# axiom_beta_plugin_module_TE0714_SDI_v0_7.net
KiCad netlist of a schematic drawn in EAGLE
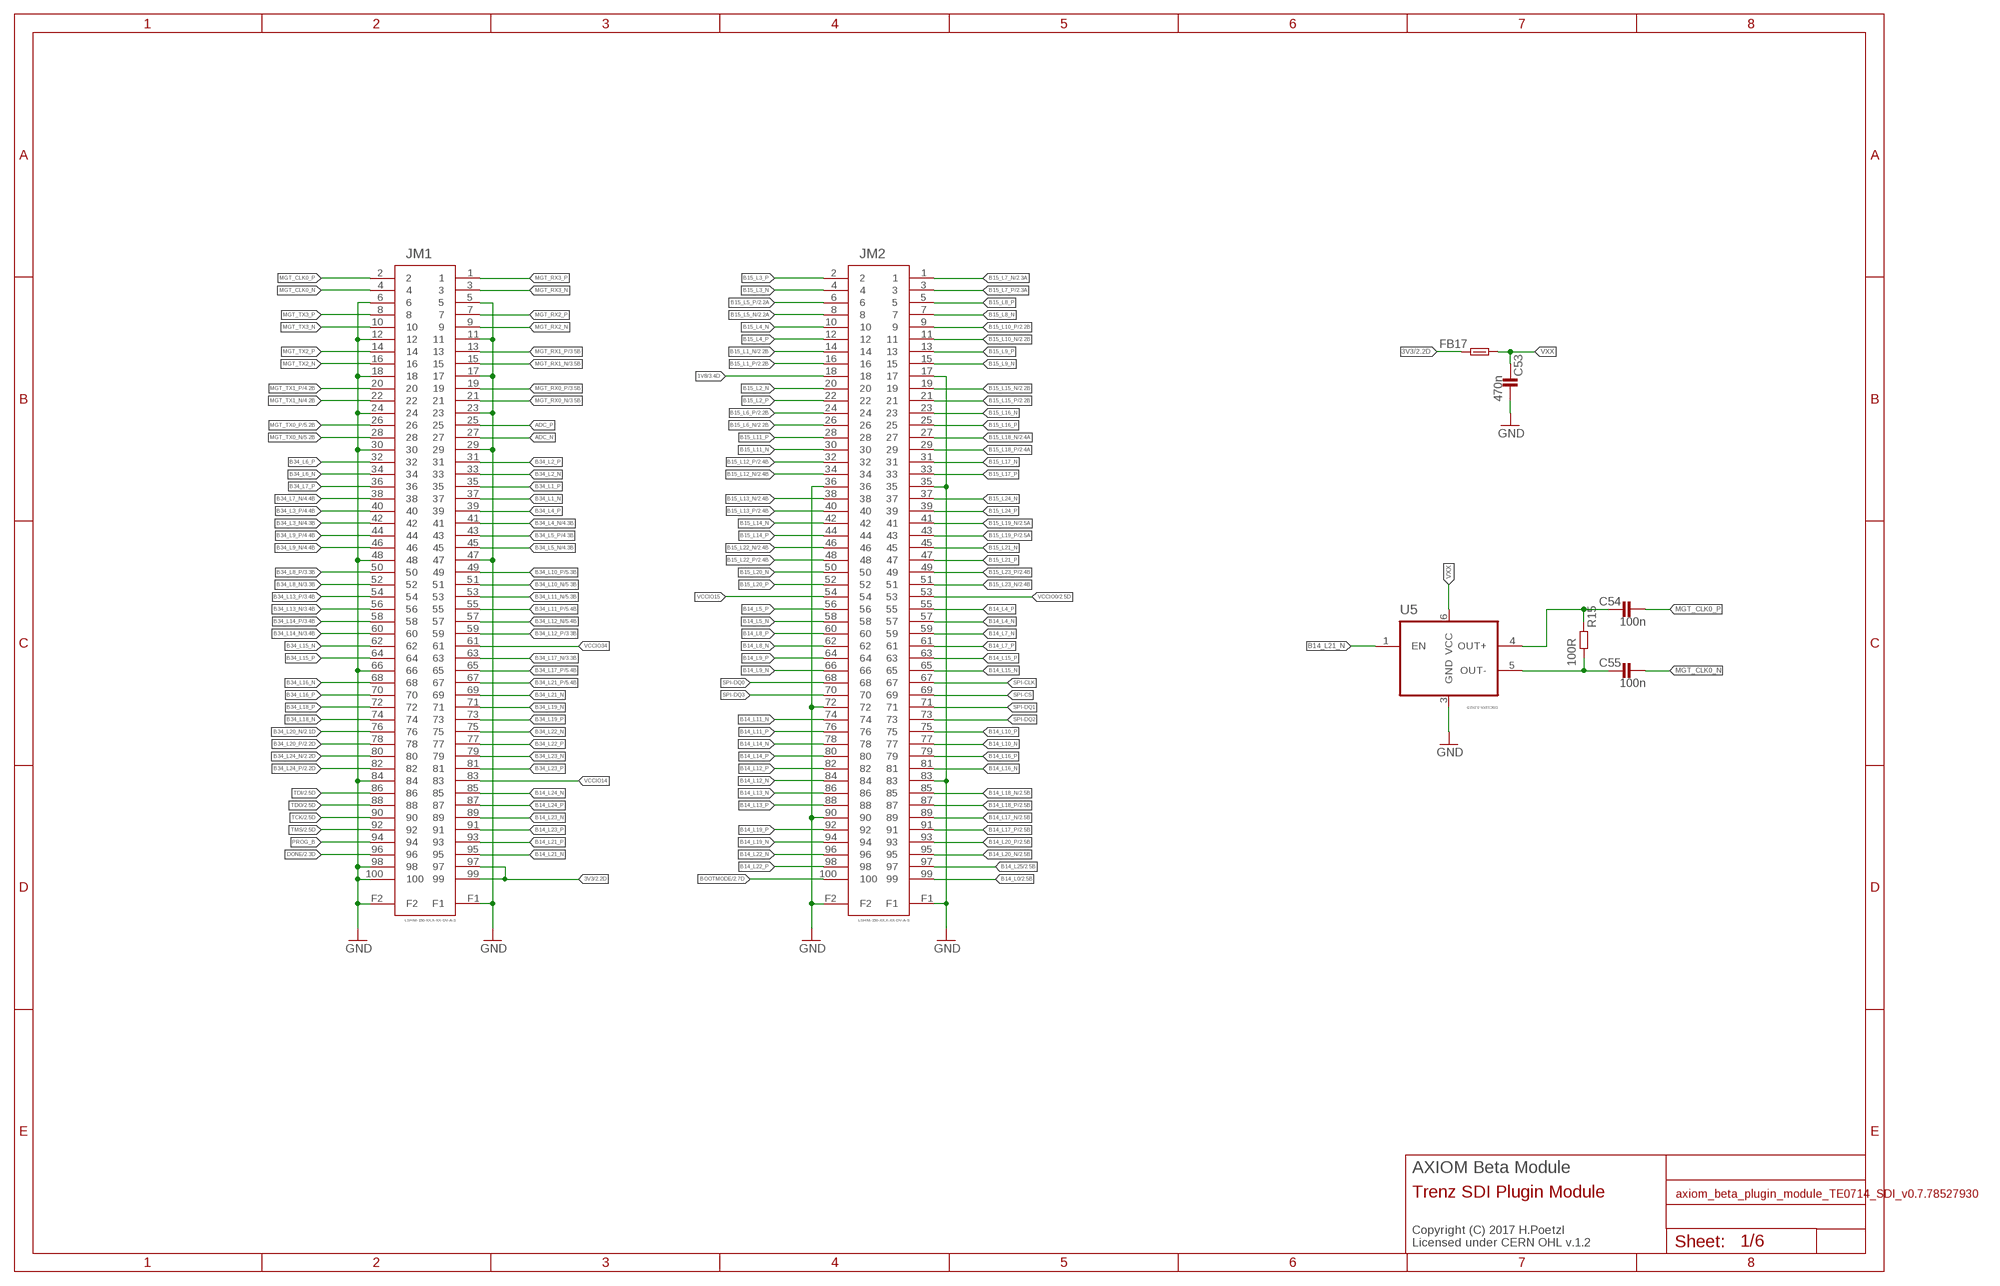
[diagram p0: schematic, sheet 1]
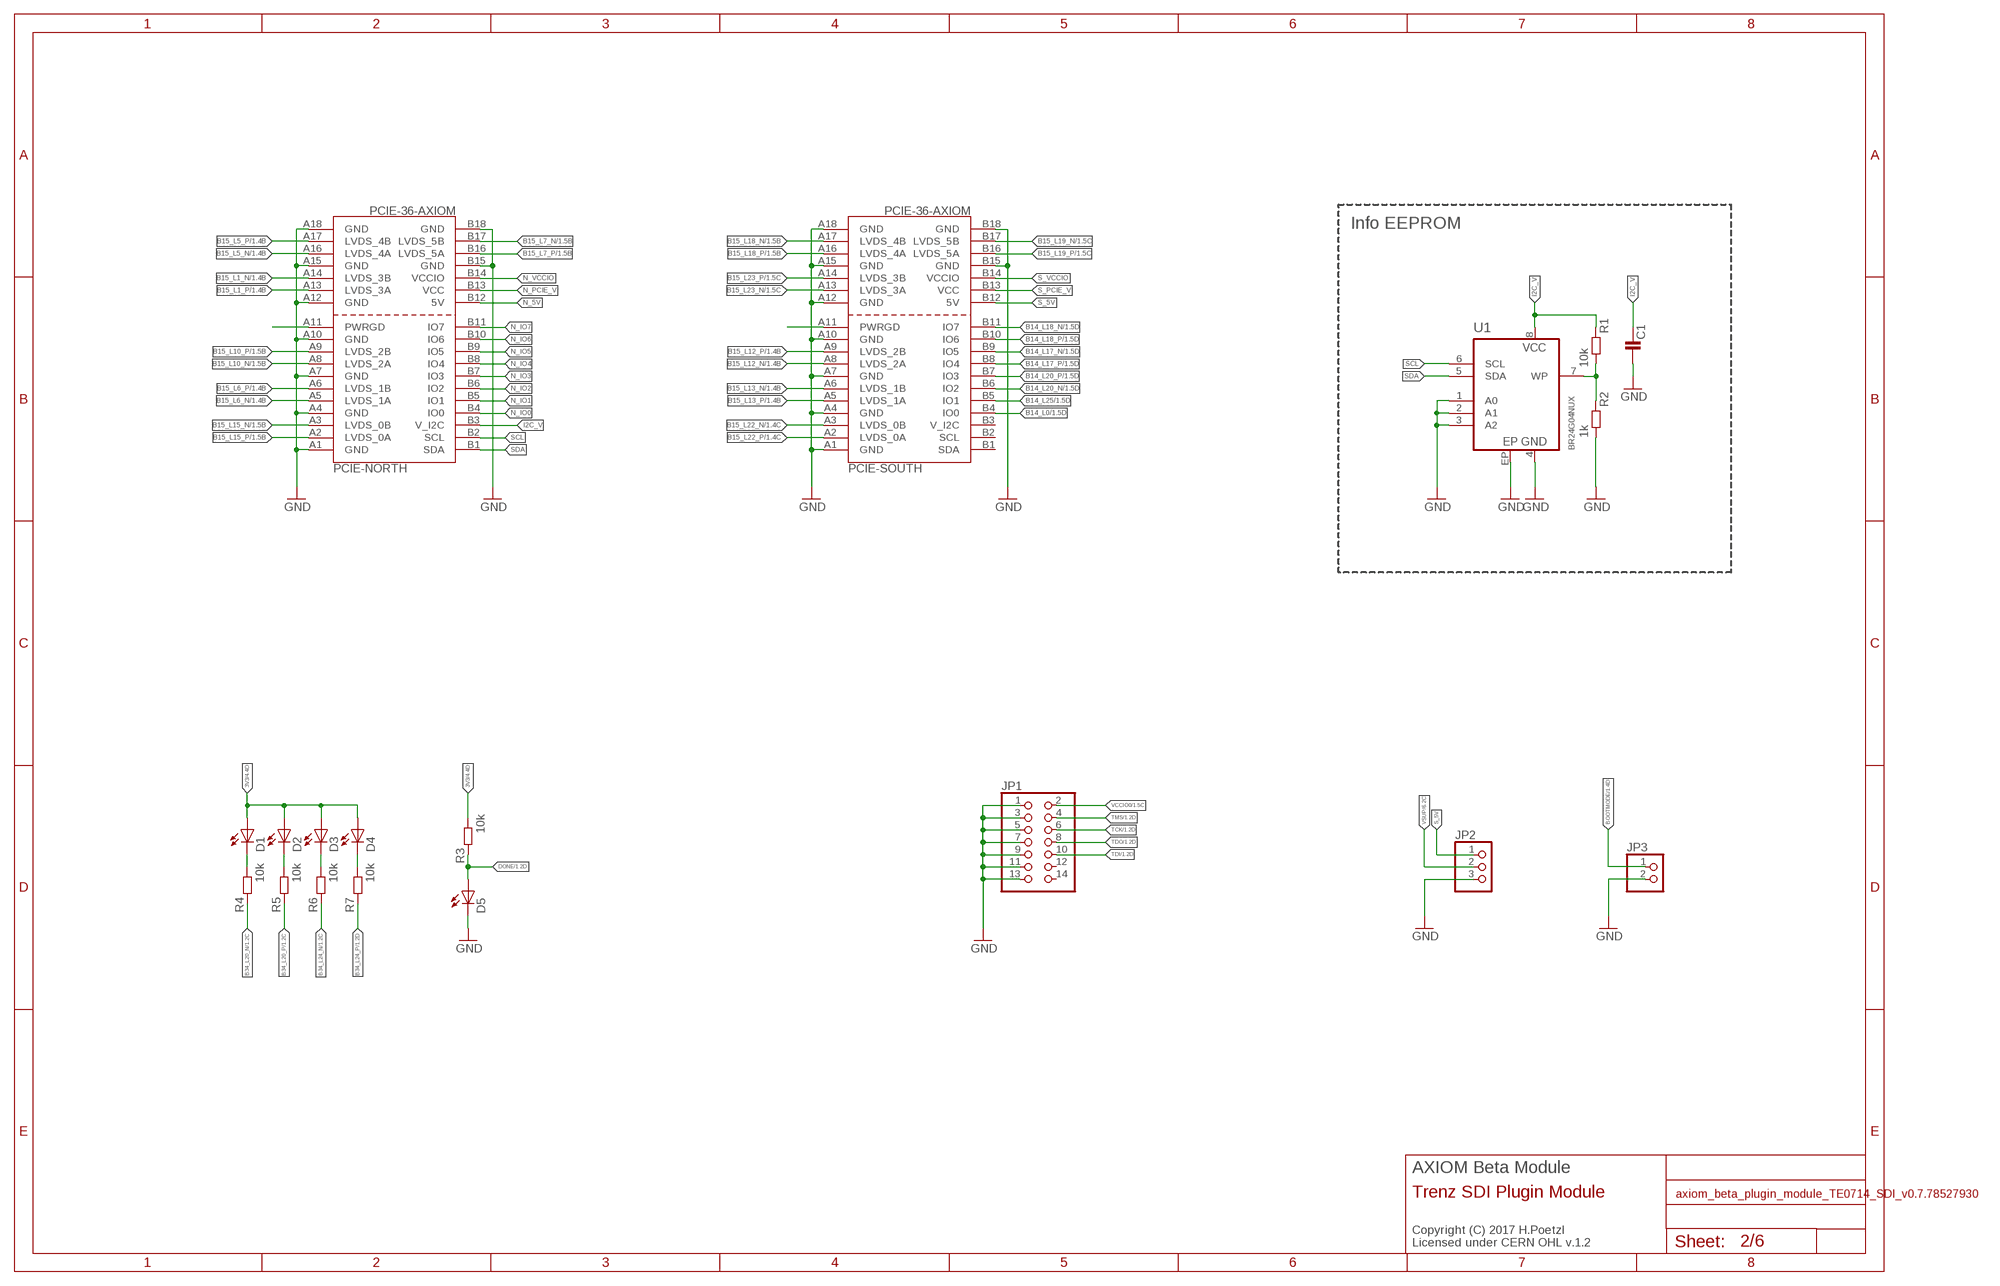
[diagram p1: schematic, sheet 2]
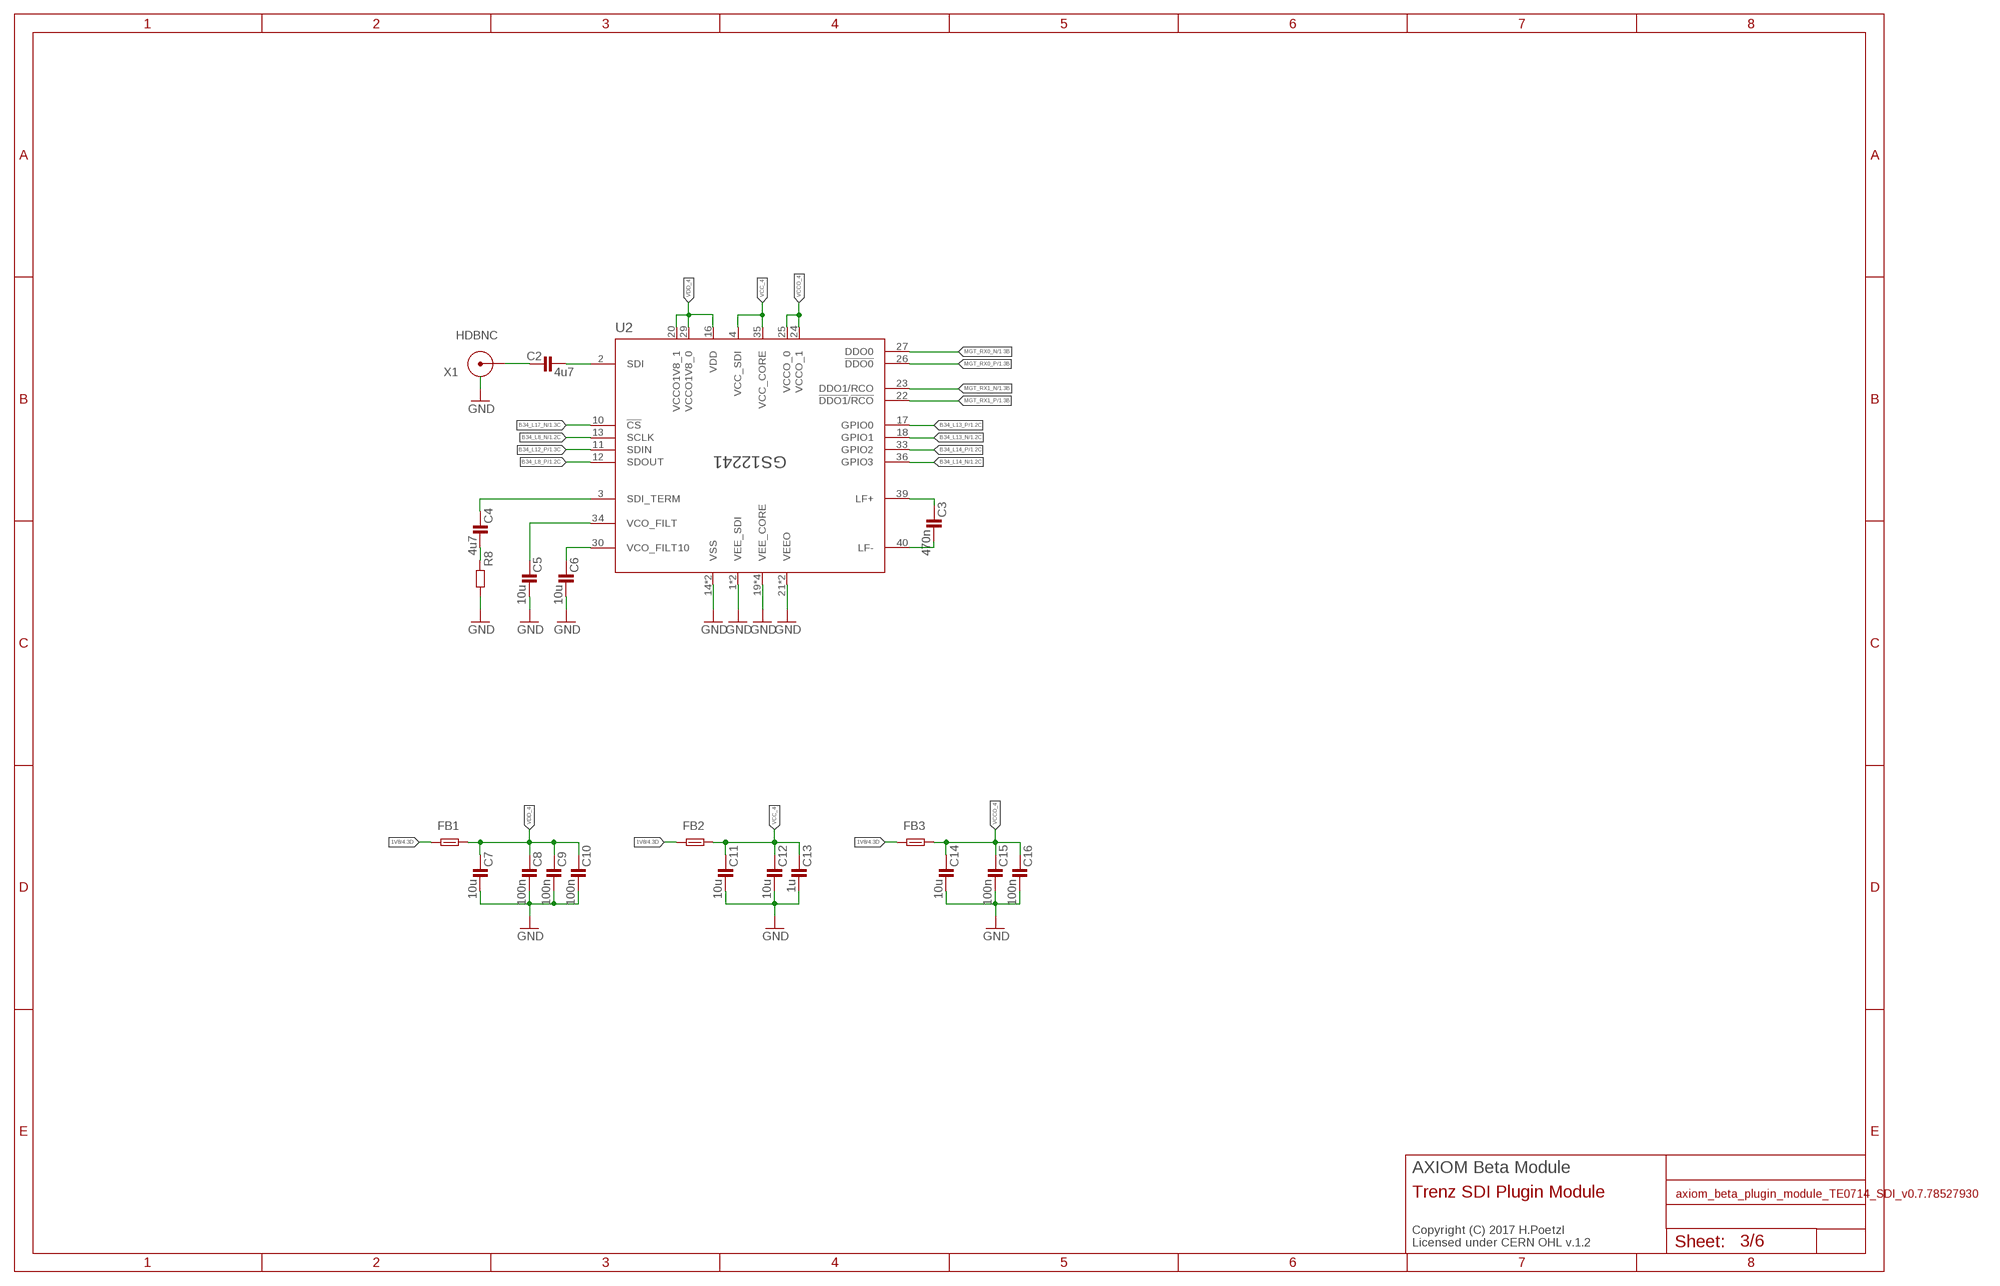
[diagram p2: schematic, sheet 3]
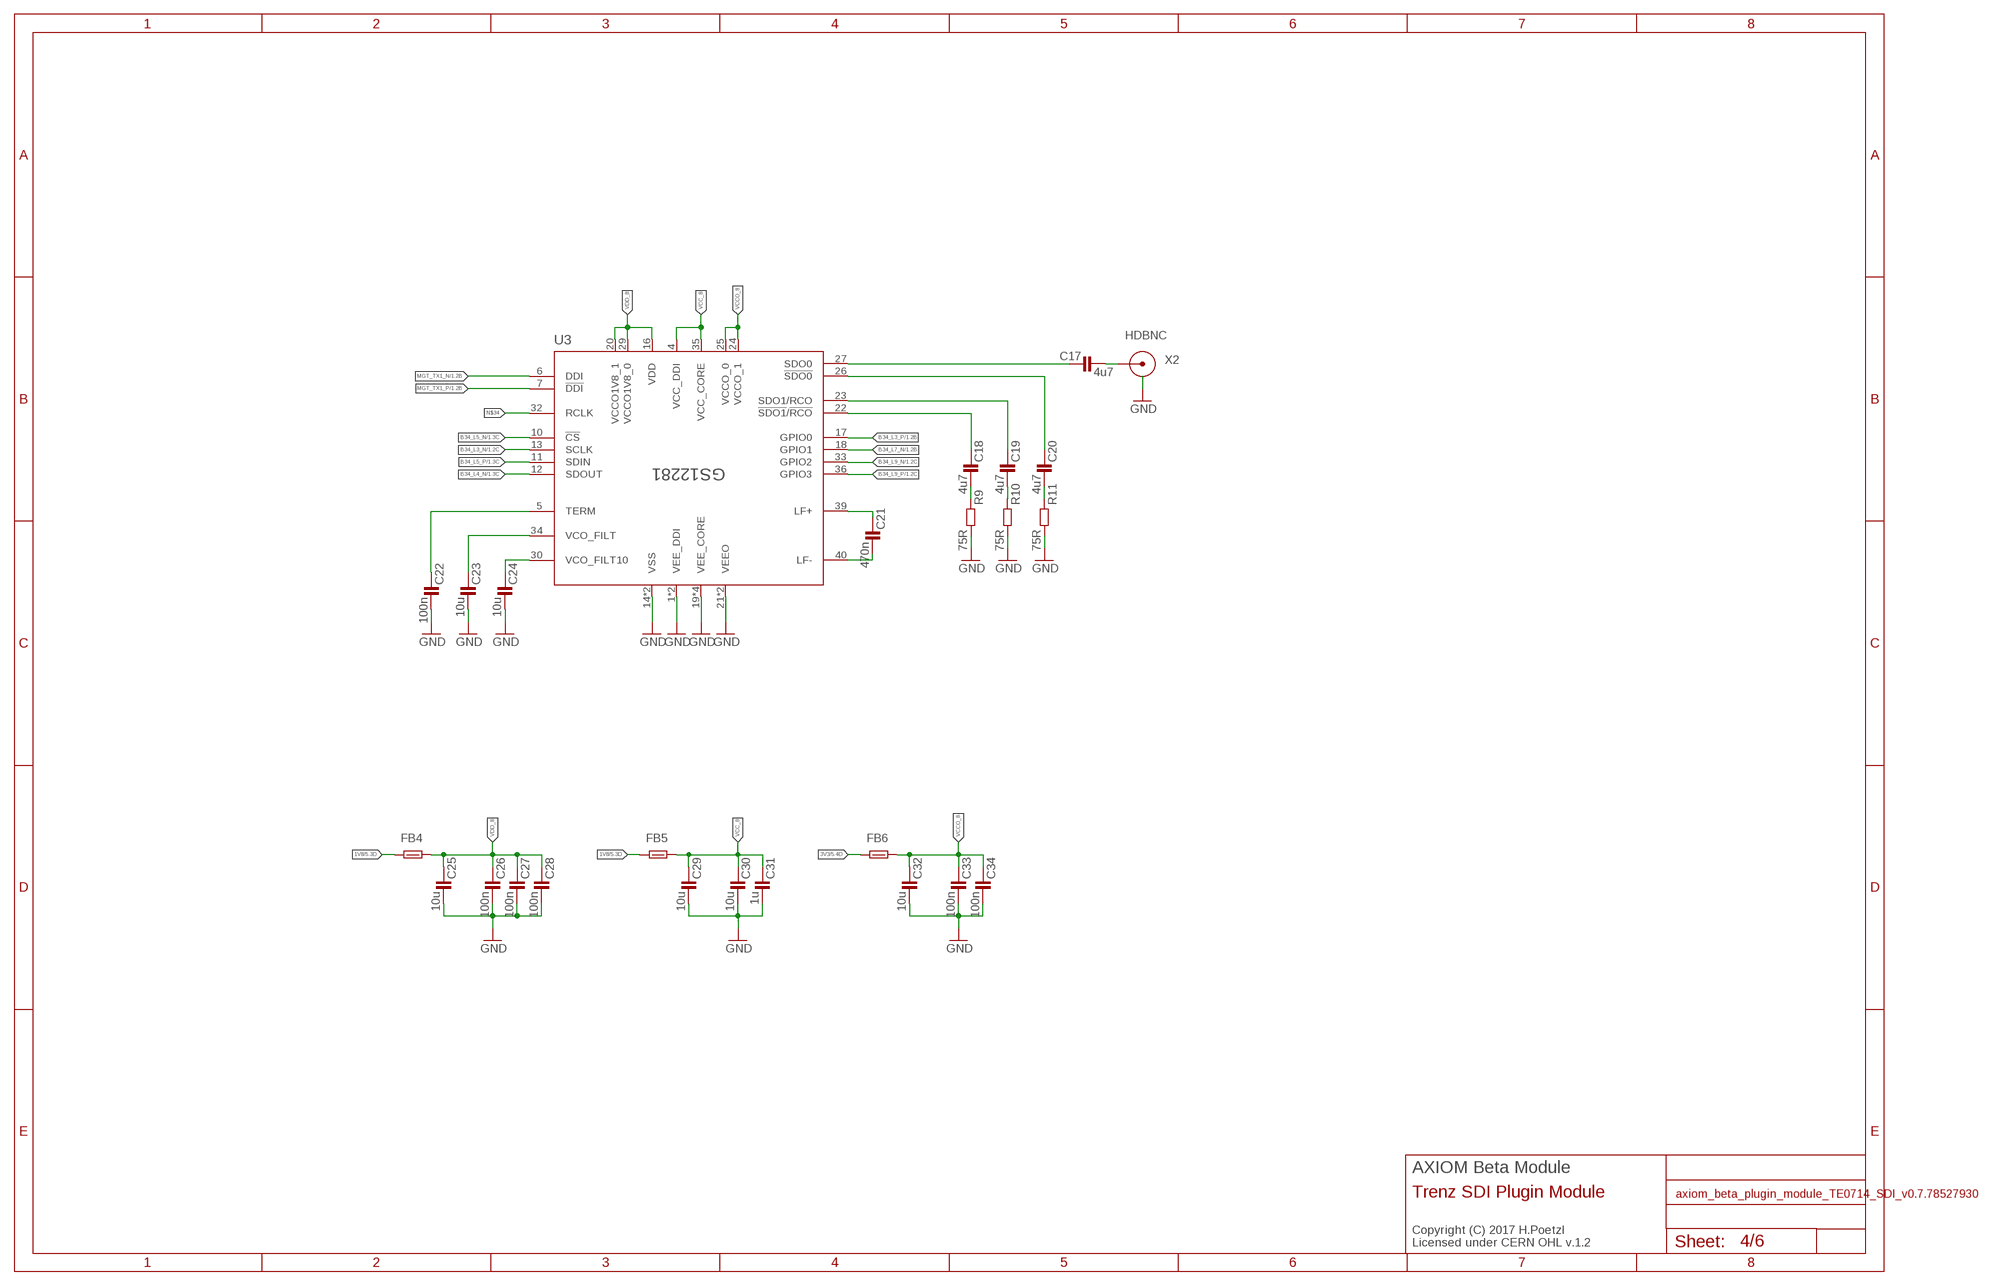
[diagram p3: schematic, sheet 4]
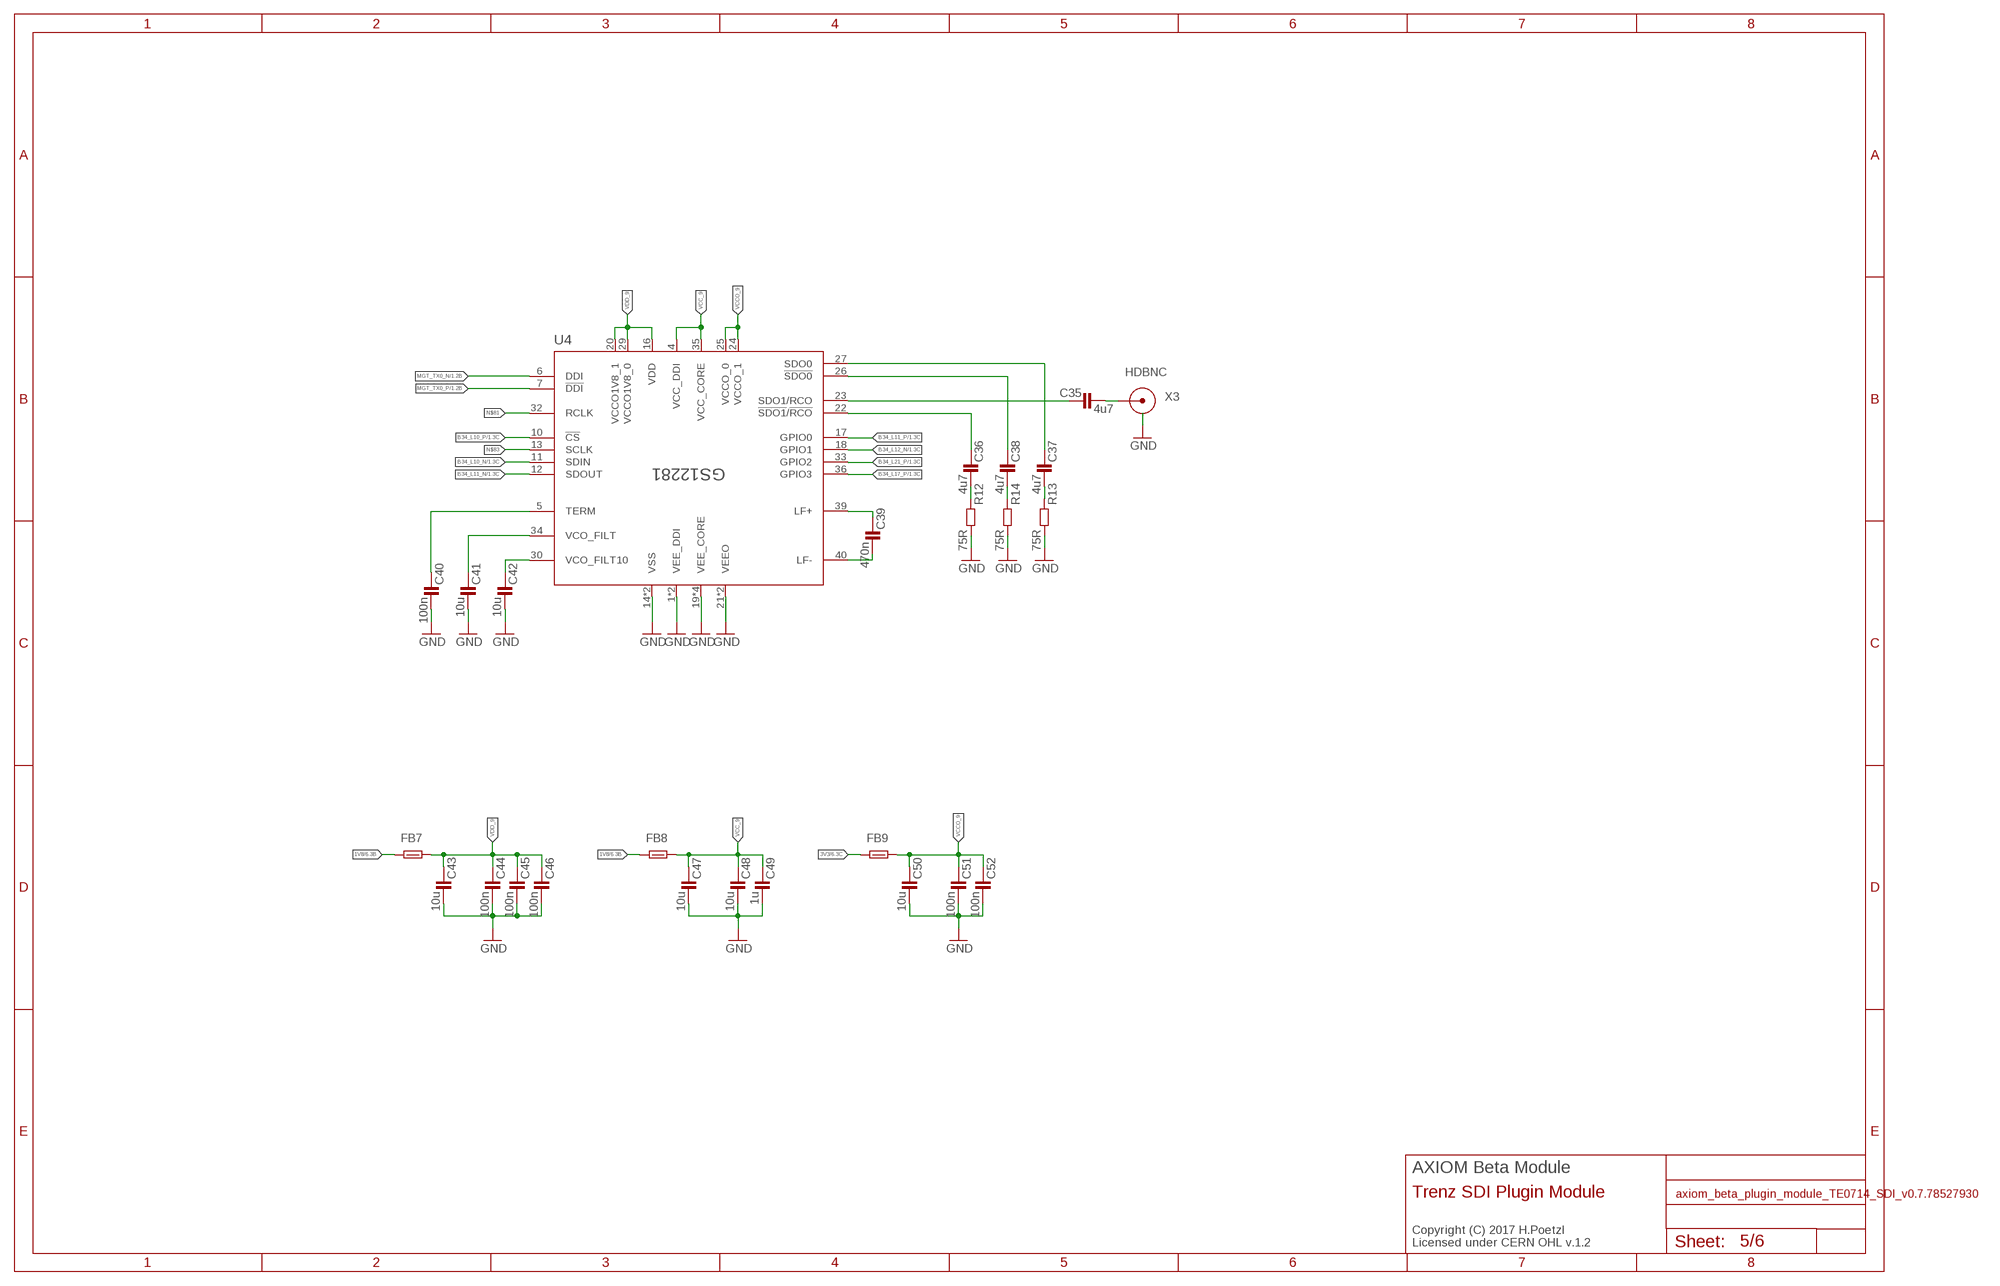
[diagram p4: schematic, sheet 5]
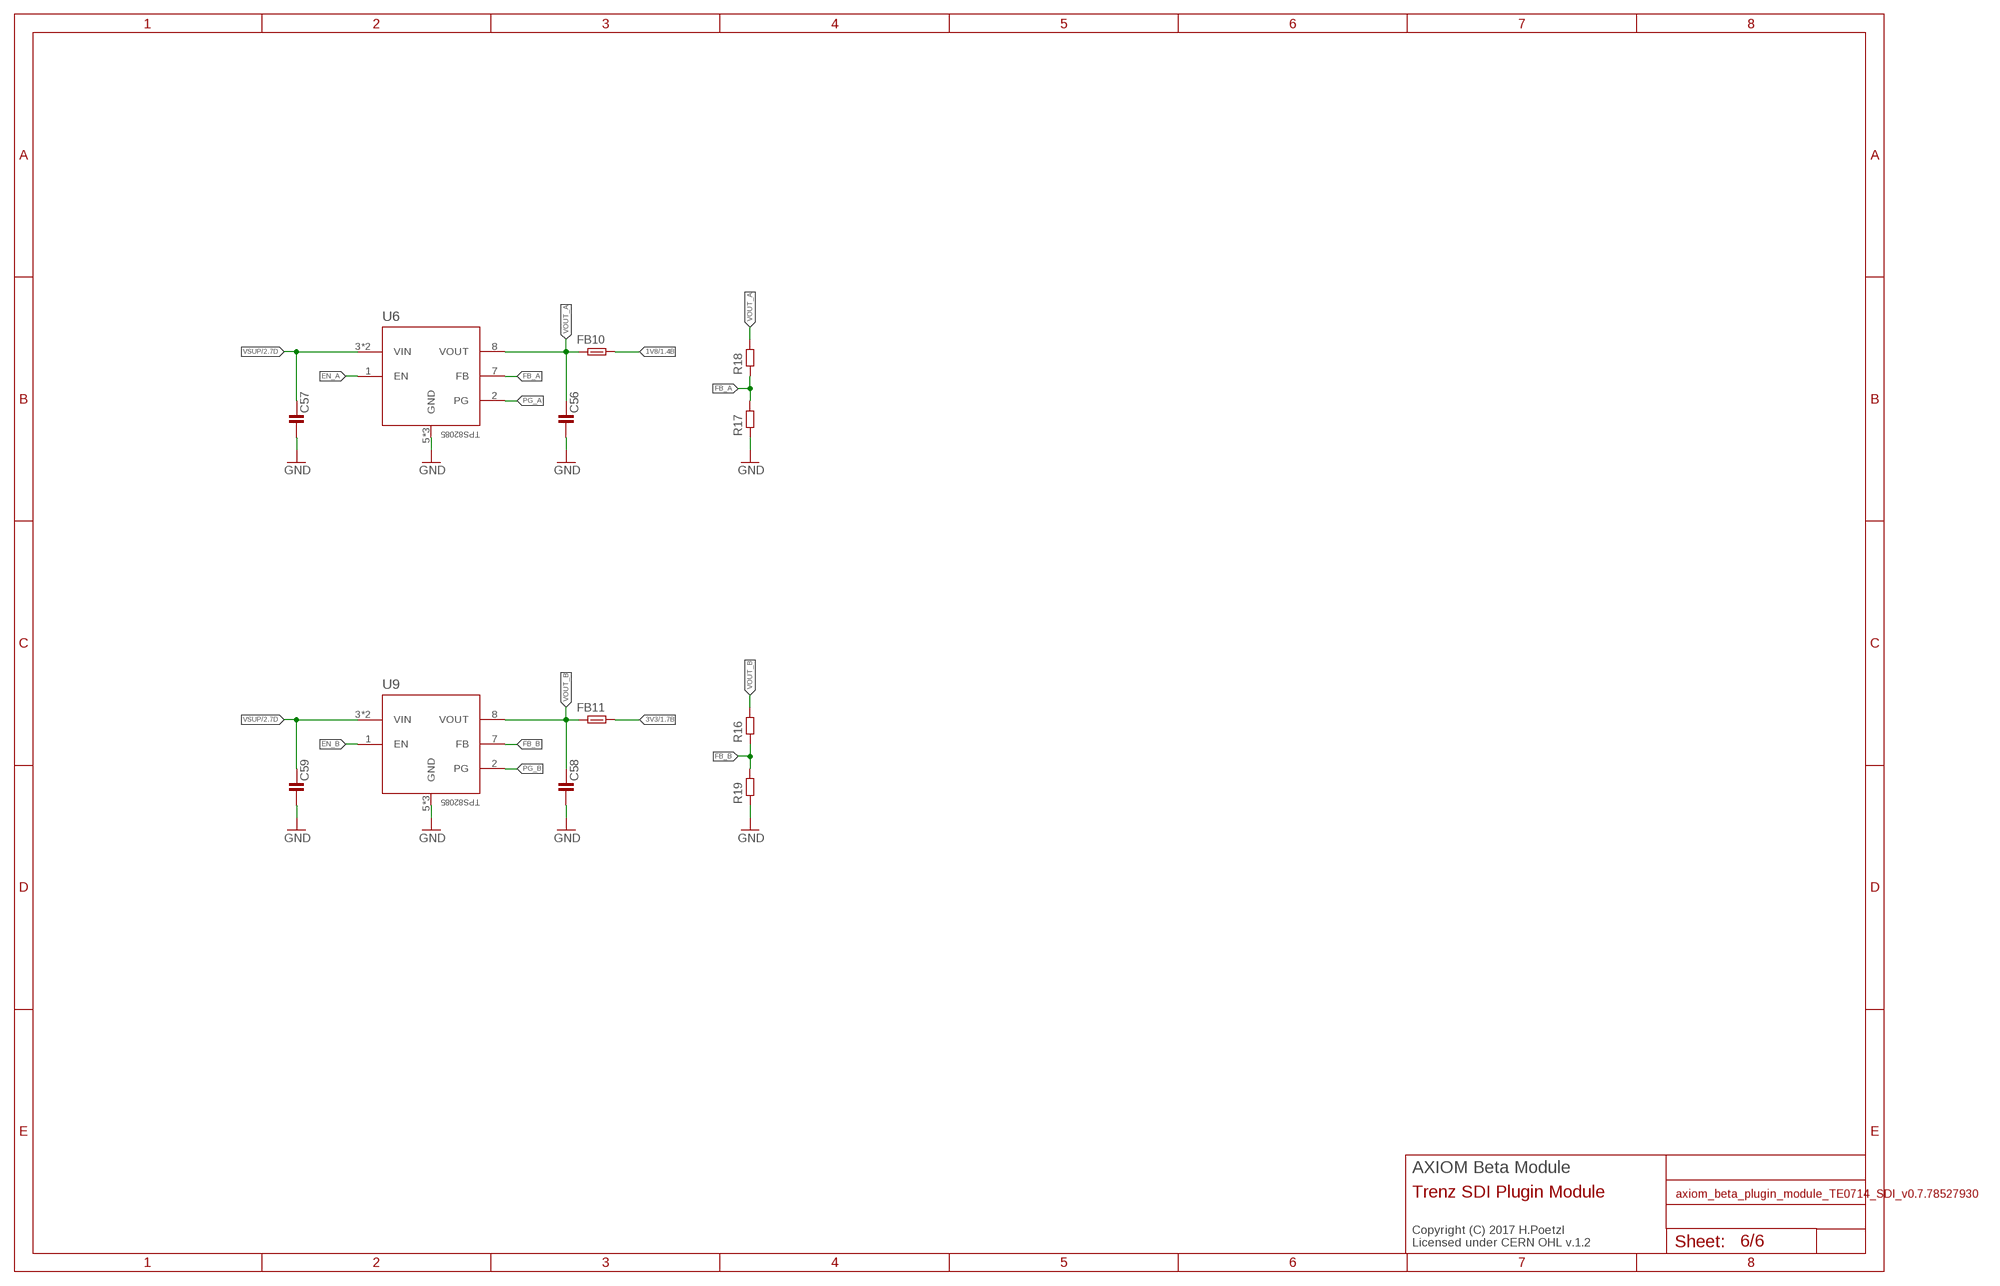
[diagram p5: schematic, sheet 6]

(export (version "E")
  (design (tool "Eeschema 10.0.6"))
  (components
    (comp (ref "C56")
      (value "C0603-C")
      (footprint "eagle-import:0603-C")
      (libsource (lib "eagle-import") (part "C0603-C"))
    )
    (comp (ref "C57")
      (value "C0603-C")
      (footprint "eagle-import:0603-C")
      (libsource (lib "eagle-import") (part "C0603-C"))
    )
    (comp (ref "C58")
      (value "C0603-C")
      (footprint "eagle-import:0603-C")
      (libsource (lib "eagle-import") (part "C0603-C"))
    )
    (comp (ref "C59")
      (value "C0603-C")
      (footprint "eagle-import:0603-C")
      (libsource (lib "eagle-import") (part "C0603-C"))
    )
    (comp (ref "FB10")
      (value "FB0603-C")
      (footprint "eagle-import:0603-C")
      (libsource (lib "eagle-import") (part "FB0603-C"))
    )
    (comp (ref "FB11")
      (value "FB0603-C")
      (footprint "eagle-import:0603-C")
      (libsource (lib "eagle-import") (part "FB0603-C"))
    )
    (comp (ref "R16")
      (value "R0201-C")
      (footprint "eagle-import:0201-C")
      (libsource (lib "eagle-import") (part "R0201-C"))
    )
    (comp (ref "R17")
      (value "R0201-C")
      (footprint "eagle-import:0201-C")
      (libsource (lib "eagle-import") (part "R0201-C"))
    )
    (comp (ref "R18")
      (value "R0201-C")
      (footprint "eagle-import:0201-C")
      (libsource (lib "eagle-import") (part "R0201-C"))
    )
    (comp (ref "R19")
      (value "R0201-C")
      (footprint "eagle-import:0201-C")
      (libsource (lib "eagle-import") (part "R0201-C"))
    )
    (comp (ref "U6")
      (value "TPS82085")
      (footprint "eagle-import:MICROSIP")
      (libsource (lib "eagle-import") (part "TPS82085"))
    )
    (comp (ref "U9")
      (value "TPS82085")
      (footprint "eagle-import:MICROSIP")
      (libsource (lib "eagle-import") (part "TPS82085"))
    )
    (comp (ref "C17")
      (value "4u7")
      (footprint "eagle-import:0402-C")
      (libsource (lib "eagle-import") (part "C0402-C"))
    )
    (comp (ref "C18")
      (value "4u7")
      (footprint "eagle-import:0402-C")
      (libsource (lib "eagle-import") (part "C0402-C"))
    )
    (comp (ref "C19")
      (value "4u7")
      (footprint "eagle-import:0402-C")
      (libsource (lib "eagle-import") (part "C0402-C"))
    )
    (comp (ref "C20")
      (value "4u7")
      (footprint "eagle-import:0402-C")
      (libsource (lib "eagle-import") (part "C0402-C"))
    )
    (comp (ref "C21")
      (value "470n")
      (footprint "eagle-import:0201-C")
      (libsource (lib "eagle-import") (part "C0201-C"))
    )
    (comp (ref "C22")
      (value "100n")
      (footprint "eagle-import:0201-C")
      (libsource (lib "eagle-import") (part "C0201-C"))
    )
    (comp (ref "C23")
      (value "10u")
      (footprint "eagle-import:0201-C")
      (libsource (lib "eagle-import") (part "C0201-C"))
    )
    (comp (ref "C24")
      (value "10u")
      (footprint "eagle-import:0402-C")
      (libsource (lib "eagle-import") (part "C0402-C"))
    )
    (comp (ref "C25")
      (value "10u")
      (footprint "eagle-import:0402-C")
      (libsource (lib "eagle-import") (part "C0402-C"))
    )
    (comp (ref "C26")
      (value "100n")
      (footprint "eagle-import:0201-C")
      (libsource (lib "eagle-import") (part "C0201-C"))
    )
    (comp (ref "C27")
      (value "100n")
      (footprint "eagle-import:0201-C")
      (libsource (lib "eagle-import") (part "C0201-C"))
    )
    (comp (ref "C28")
      (value "100n")
      (footprint "eagle-import:0201-C")
      (libsource (lib "eagle-import") (part "C0201-C"))
    )
    (comp (ref "C29")
      (value "10u")
      (footprint "eagle-import:0402-C")
      (libsource (lib "eagle-import") (part "C0402-C"))
    )
    (comp (ref "C30")
      (value "10u")
      (footprint "eagle-import:0402-C")
      (libsource (lib "eagle-import") (part "C0402-C"))
    )
    (comp (ref "C31")
      (value "1u")
      (footprint "eagle-import:0201-C")
      (libsource (lib "eagle-import") (part "C0201-C"))
    )
    (comp (ref "C32")
      (value "10u")
      (footprint "eagle-import:0402-C")
      (libsource (lib "eagle-import") (part "C0402-C"))
    )
    (comp (ref "C33")
      (value "100n")
      (footprint "eagle-import:0201-C")
      (libsource (lib "eagle-import") (part "C0201-C"))
    )
    (comp (ref "C34")
      (value "100n")
      (footprint "eagle-import:0201-C")
      (libsource (lib "eagle-import") (part "C0201-C"))
    )
    (comp (ref "FB4")
      (value "FB0402-C")
      (footprint "eagle-import:0402-C")
      (libsource (lib "eagle-import") (part "FB0402-C"))
    )
    (comp (ref "FB5")
      (value "FB0402-C")
      (footprint "eagle-import:0402-C")
      (libsource (lib "eagle-import") (part "FB0402-C"))
    )
    (comp (ref "FB6")
      (value "FB0402-C")
      (footprint "eagle-import:0402-C")
      (libsource (lib "eagle-import") (part "FB0402-C"))
    )
    (comp (ref "R9")
      (value "75R")
      (footprint "eagle-import:0201-C")
      (libsource (lib "eagle-import") (part "R0201-C"))
    )
    (comp (ref "R10")
      (value "75R")
      (footprint "eagle-import:0201-C")
      (libsource (lib "eagle-import") (part "R0201-C"))
    )
    (comp (ref "R11")
      (value "75R")
      (footprint "eagle-import:0201-C")
      (libsource (lib "eagle-import") (part "R0201-C"))
    )
    (comp (ref "U3")
      (value "GS12281")
      (footprint "eagle-import:UQFN40P600X400X100-41N")
      (libsource (lib "eagle-import") (part "GS12281"))
    )
    (comp (ref "X2")
      (value "HDBNC")
      (footprint "eagle-import:HDBNC_EDGE_2SIDE")
      (libsource (lib "eagle-import") (part "HDBNC"))
    )
    (comp (ref "C1")
      (value "C0402-B")
      (footprint "eagle-import:0402-B")
      (libsource (lib "eagle-import") (part "C0402-B"))
    )
    (comp (ref "D1")
      (value "LED")
      (footprint "eagle-import:CHIPLED_0603")
      (libsource (lib "eagle-import") (part "LED"))
    )
    (comp (ref "D2")
      (value "LED")
      (footprint "eagle-import:CHIPLED_0603")
      (libsource (lib "eagle-import") (part "LED"))
    )
    (comp (ref "D3")
      (value "LED")
      (footprint "eagle-import:CHIPLED_0603")
      (libsource (lib "eagle-import") (part "LED"))
    )
    (comp (ref "D4")
      (value "LED")
      (footprint "eagle-import:CHIPLED_0603")
      (libsource (lib "eagle-import") (part "LED"))
    )
    (comp (ref "D5")
      (value "LED")
      (footprint "eagle-import:CHIPLED_0603")
      (libsource (lib "eagle-import") (part "LED"))
    )
    (comp (ref "JP1")
      (value "PINHD-2X07_2.00")
      (footprint "eagle-import:2X07M")
      (libsource (lib "eagle-import") (part "PINHD-2X07_2.00"))
    )
    (comp (ref "JP2")
      (value "PINHD-1X03_2.54-90°-S")
      (footprint "eagle-import:1X03_90-S")
      (libsource (lib "eagle-import") (part "PINHD-1X03_2.54-90°-S"))
    )
    (comp (ref "JP3")
      (value "PINHD-1X02_2.54-S")
      (footprint "eagle-import:1X02-S")
      (libsource (lib "eagle-import") (part "PINHD-1X02_2.54-S"))
    )
    (comp (ref "PCIE-NORTH")
      (value "PCIE-36-AXIOM")
      (footprint "eagle-import:PCIE-36-AXIOM")
      (libsource (lib "eagle-import") (part "PCIE-36-AXIOM"))
    )
    (comp (ref "PCIE-SOUTH")
      (value "PCIE-36-AXIOM")
      (footprint "eagle-import:PCIE-36-AXIOM")
      (libsource (lib "eagle-import") (part "PCIE-36-AXIOM"))
    )
    (comp (ref "R1")
      (value "10k")
      (footprint "eagle-import:0402-B")
      (libsource (lib "eagle-import") (part "R0402-B"))
    )
    (comp (ref "R2")
      (value "1k")
      (footprint "eagle-import:0402-B")
      (libsource (lib "eagle-import") (part "R0402-B"))
    )
    (comp (ref "R3")
      (value "10k")
      (footprint "eagle-import:0402-C")
      (libsource (lib "eagle-import") (part "R0402-C"))
    )
    (comp (ref "R4")
      (value "10k")
      (footprint "eagle-import:0402-C")
      (libsource (lib "eagle-import") (part "R0402-C"))
    )
    (comp (ref "R5")
      (value "10k")
      (footprint "eagle-import:0402-C")
      (libsource (lib "eagle-import") (part "R0402-C"))
    )
    (comp (ref "R6")
      (value "10k")
      (footprint "eagle-import:0402-C")
      (libsource (lib "eagle-import") (part "R0402-C"))
    )
    (comp (ref "R7")
      (value "10k")
      (footprint "eagle-import:0402-C")
      (libsource (lib "eagle-import") (part "R0402-C"))
    )
    (comp (ref "U1")
      (value "BR24G04NUX")
      (footprint "eagle-import:DFN200X300X100-9N")
      (libsource (lib "eagle-import") (part "BR24G04NUX"))
    )
    (comp (ref "C35")
      (value "4u7")
      (footprint "eagle-import:0402-C")
      (libsource (lib "eagle-import") (part "C0402-C"))
    )
    (comp (ref "C36")
      (value "4u7")
      (footprint "eagle-import:0402-C")
      (libsource (lib "eagle-import") (part "C0402-C"))
    )
    (comp (ref "C37")
      (value "4u7")
      (footprint "eagle-import:0402-C")
      (libsource (lib "eagle-import") (part "C0402-C"))
    )
    (comp (ref "C38")
      (value "4u7")
      (footprint "eagle-import:0402-C")
      (libsource (lib "eagle-import") (part "C0402-C"))
    )
    (comp (ref "C39")
      (value "470n")
      (footprint "eagle-import:0201-C")
      (libsource (lib "eagle-import") (part "C0201-C"))
    )
    (comp (ref "C40")
      (value "100n")
      (footprint "eagle-import:0201-C")
      (libsource (lib "eagle-import") (part "C0201-C"))
    )
    (comp (ref "C41")
      (value "10u")
      (footprint "eagle-import:0402-C")
      (libsource (lib "eagle-import") (part "C0402-C"))
    )
    (comp (ref "C42")
      (value "10u")
      (footprint "eagle-import:0402-C")
      (libsource (lib "eagle-import") (part "C0402-C"))
    )
    (comp (ref "C43")
      (value "10u")
      (footprint "eagle-import:0402-C")
      (libsource (lib "eagle-import") (part "C0402-C"))
    )
    (comp (ref "C44")
      (value "100n")
      (footprint "eagle-import:0201-C")
      (libsource (lib "eagle-import") (part "C0201-C"))
    )
    (comp (ref "C45")
      (value "100n")
      (footprint "eagle-import:0201-C")
      (libsource (lib "eagle-import") (part "C0201-C"))
    )
    (comp (ref "C46")
      (value "100n")
      (footprint "eagle-import:0201-C")
      (libsource (lib "eagle-import") (part "C0201-C"))
    )
    (comp (ref "C47")
      (value "10u")
      (footprint "eagle-import:0402-C")
      (libsource (lib "eagle-import") (part "C0402-C"))
    )
    (comp (ref "C48")
      (value "10u")
      (footprint "eagle-import:0402-C")
      (libsource (lib "eagle-import") (part "C0402-C"))
    )
    (comp (ref "C49")
      (value "1u")
      (footprint "eagle-import:0201-C")
      (libsource (lib "eagle-import") (part "C0201-C"))
    )
    (comp (ref "C50")
      (value "10u")
      (footprint "eagle-import:0402-C")
      (libsource (lib "eagle-import") (part "C0402-C"))
    )
    (comp (ref "C51")
      (value "100n")
      (footprint "eagle-import:0201-C")
      (libsource (lib "eagle-import") (part "C0201-C"))
    )
    (comp (ref "C52")
      (value "100n")
      (footprint "eagle-import:0201-C")
      (libsource (lib "eagle-import") (part "C0201-C"))
    )
    (comp (ref "FB7")
      (value "FB0402-C")
      (footprint "eagle-import:0402-C")
      (libsource (lib "eagle-import") (part "FB0402-C"))
    )
    (comp (ref "FB8")
      (value "FB0402-C")
      (footprint "eagle-import:0402-C")
      (libsource (lib "eagle-import") (part "FB0402-C"))
    )
    (comp (ref "FB9")
      (value "FB0402-C")
      (footprint "eagle-import:0402-C")
      (libsource (lib "eagle-import") (part "FB0402-C"))
    )
    (comp (ref "R12")
      (value "75R")
      (footprint "eagle-import:0201-C")
      (libsource (lib "eagle-import") (part "R0201-C"))
    )
    (comp (ref "R13")
      (value "75R")
      (footprint "eagle-import:0201-C")
      (libsource (lib "eagle-import") (part "R0201-C"))
    )
    (comp (ref "R14")
      (value "75R")
      (footprint "eagle-import:0201-C")
      (libsource (lib "eagle-import") (part "R0201-C"))
    )
    (comp (ref "U4")
      (value "GS12281")
      (footprint "eagle-import:UQFN40P600X400X100-41N")
      (libsource (lib "eagle-import") (part "GS12281"))
    )
    (comp (ref "X3")
      (value "HDBNC")
      (footprint "eagle-import:HDBNC_EDGE_2SIDE")
      (libsource (lib "eagle-import") (part "HDBNC"))
    )
    (comp (ref "C53")
      (value "470n")
      (footprint "eagle-import:0402-C")
      (libsource (lib "eagle-import") (part "C0402-C"))
    )
    (comp (ref "C54")
      (value "100n")
      (footprint "eagle-import:0201-C")
      (libsource (lib "eagle-import") (part "C0201-C"))
    )
    (comp (ref "C55")
      (value "100n")
      (footprint "eagle-import:0201-C")
      (libsource (lib "eagle-import") (part "C0201-C"))
    )
    (comp (ref "FB17")
      (value "FB0402-C")
      (footprint "eagle-import:0402-C")
      (libsource (lib "eagle-import") (part "FB0402-C"))
    )
    (comp (ref "JM1")
      (value "LSHM-150-XX.X-XX-DV-A-S")
      (footprint "eagle-import:LSHM-150-XX.X-XX-DV-A-S")
      (libsource (lib "eagle-import") (part "LSHM-150-XX.X-XX-DV-A-S"))
    )
    (comp (ref "JM2")
      (value "LSHM-150-XX.X-XX-DV-A-S")
      (footprint "eagle-import:LSHM-150-XX.X-XX-DV-A-S")
      (libsource (lib "eagle-import") (part "LSHM-150-XX.X-XX-DV-A-S"))
    )
    (comp (ref "R15")
      (value "100R")
      (footprint "eagle-import:0201-C")
      (libsource (lib "eagle-import") (part "R0201-C"))
    )
    (comp (ref "U5")
      (value "DSC11XX-3.2X2.5")
      (footprint "eagle-import:3.2X2.5")
      (libsource (lib "eagle-import") (part "DSC11XX-3.2X2.5"))
    )
    (comp (ref "C2")
      (value "4u7")
      (footprint "eagle-import:0402-C")
      (libsource (lib "eagle-import") (part "C0402-C"))
    )
    (comp (ref "C3")
      (value "470n")
      (footprint "eagle-import:0201-C")
      (libsource (lib "eagle-import") (part "C0201-C"))
    )
    (comp (ref "C4")
      (value "4u7")
      (footprint "eagle-import:0402-C")
      (libsource (lib "eagle-import") (part "C0402-C"))
    )
    (comp (ref "C5")
      (value "10u")
      (footprint "eagle-import:0201-C")
      (libsource (lib "eagle-import") (part "C0201-C"))
    )
    (comp (ref "C6")
      (value "10u")
      (footprint "eagle-import:0402-C")
      (libsource (lib "eagle-import") (part "C0402-C"))
    )
    (comp (ref "C7")
      (value "10u")
      (footprint "eagle-import:0402-C")
      (libsource (lib "eagle-import") (part "C0402-C"))
    )
    (comp (ref "C8")
      (value "100n")
      (footprint "eagle-import:0201-C")
      (libsource (lib "eagle-import") (part "C0201-C"))
    )
    (comp (ref "C9")
      (value "100n")
      (footprint "eagle-import:0201-C")
      (libsource (lib "eagle-import") (part "C0201-C"))
    )
    (comp (ref "C10")
      (value "100n")
      (footprint "eagle-import:0201-C")
      (libsource (lib "eagle-import") (part "C0201-C"))
    )
    (comp (ref "C11")
      (value "10u")
      (footprint "eagle-import:0402-C")
      (libsource (lib "eagle-import") (part "C0402-C"))
    )
    (comp (ref "C12")
      (value "10u")
      (footprint "eagle-import:0402-C")
      (libsource (lib "eagle-import") (part "C0402-C"))
    )
    (comp (ref "C13")
      (value "1u")
      (footprint "eagle-import:0201-C")
      (libsource (lib "eagle-import") (part "C0201-C"))
    )
    (comp (ref "C14")
      (value "10u")
      (footprint "eagle-import:0402-C")
      (libsource (lib "eagle-import") (part "C0402-C"))
    )
    (comp (ref "C15")
      (value "100n")
      (footprint "eagle-import:0201-C")
      (libsource (lib "eagle-import") (part "C0201-C"))
    )
    (comp (ref "C16")
      (value "100n")
      (footprint "eagle-import:0201-C")
      (libsource (lib "eagle-import") (part "C0201-C"))
    )
    (comp (ref "FB1")
      (value "FB0402-C")
      (footprint "eagle-import:0402-C")
      (libsource (lib "eagle-import") (part "FB0402-C"))
    )
    (comp (ref "FB2")
      (value "FB0402-C")
      (footprint "eagle-import:0402-C")
      (libsource (lib "eagle-import") (part "FB0402-C"))
    )
    (comp (ref "FB3")
      (value "FB0402-C")
      (footprint "eagle-import:0402-C")
      (libsource (lib "eagle-import") (part "FB0402-C"))
    )
    (comp (ref "R8")
      (value "R0201-C")
      (footprint "eagle-import:0201-C")
      (libsource (lib "eagle-import") (part "R0201-C"))
    )
    (comp (ref "U2")
      (value "GS12241")
      (footprint "eagle-import:UQFN40P600X400X100-41N")
      (libsource (lib "eagle-import") (part "GS12241"))
    )
    (comp (ref "X1")
      (value "HDBNC")
      (footprint "eagle-import:HDBNC_EDGE_2SIDE")
      (libsource (lib "eagle-import") (part "HDBNC"))
    )
  )
  (nets
    (net (code "1") (name "1V8") (class "Default")
      (node (ref "FB1") (pin "1") (pinfunction "1_1") (pintype "passive"))
      (node (ref "FB10") (pin "2") (pinfunction "2_2") (pintype "passive"))
      (node (ref "FB2") (pin "1") (pinfunction "1_1") (pintype "passive"))
      (node (ref "FB3") (pin "1") (pinfunction "1_1") (pintype "passive"))
      (node (ref "FB4") (pin "1") (pinfunction "1_1") (pintype "passive"))
      (node (ref "FB5") (pin "1") (pinfunction "1_1") (pintype "passive"))
      (node (ref "FB7") (pin "1") (pinfunction "1_1") (pintype "passive"))
      (node (ref "FB8") (pin "1") (pinfunction "1_1") (pintype "passive"))
      (node (ref "JM2") (pin "18") (pinfunction "18_18") (pintype "bidirectional"))
    )
    (net (code "2") (name "3V3") (class "Default")
      (node (ref "D1") (pin "A") (pinfunction "A_A") (pintype "passive"))
      (node (ref "D2") (pin "A") (pinfunction "A_A") (pintype "passive"))
      (node (ref "D3") (pin "A") (pinfunction "A_A") (pintype "passive"))
      (node (ref "D4") (pin "A") (pinfunction "A_A") (pintype "passive"))
      (node (ref "FB11") (pin "2") (pinfunction "2_2") (pintype "passive"))
      (node (ref "FB17") (pin "1") (pinfunction "1_1") (pintype "passive"))
      (node (ref "FB6") (pin "1") (pinfunction "1_1") (pintype "passive"))
      (node (ref "FB9") (pin "1") (pinfunction "1_1") (pintype "passive"))
      (node (ref "JM1") (pin "97") (pinfunction "97_97") (pintype "bidirectional"))
      (node (ref "JM1") (pin "99") (pinfunction "99_99") (pintype "bidirectional"))
      (node (ref "R3") (pin "2") (pinfunction "2_2") (pintype "passive"))
    )
    (net (code "3") (name "ADC_N") (class "Default")
      (node (ref "JM1") (pin "27") (pinfunction "27_27") (pintype "bidirectional"))
    )
    (net (code "4") (name "ADC_P") (class "Default")
      (node (ref "JM1") (pin "25") (pinfunction "25_25") (pintype "bidirectional"))
    )
    (net (code "5") (name "B14_L0") (class "Default")
      (node (ref "JM2") (pin "99") (pinfunction "99_99") (pintype "bidirectional"))
      (node (ref "PCIE-SOUTH") (pin "B4") (pinfunction "IO0_B4") (pintype "passive"))
    )
    (net (code "6") (name "B14_L4_N") (class "Default")
      (node (ref "JM2") (pin "57") (pinfunction "57_57") (pintype "bidirectional"))
    )
    (net (code "7") (name "B14_L4_P") (class "Default")
      (node (ref "JM2") (pin "55") (pinfunction "55_55") (pintype "bidirectional"))
    )
    (net (code "8") (name "B14_L5_N") (class "Default")
      (node (ref "JM2") (pin "58") (pinfunction "58_58") (pintype "bidirectional"))
    )
    (net (code "9") (name "B14_L5_P") (class "Default")
      (node (ref "JM2") (pin "56") (pinfunction "56_56") (pintype "bidirectional"))
    )
    (net (code "10") (name "B14_L7_N") (class "Default")
      (node (ref "JM2") (pin "59") (pinfunction "59_59") (pintype "bidirectional"))
    )
    (net (code "11") (name "B14_L7_P") (class "Default")
      (node (ref "JM2") (pin "61") (pinfunction "61_61") (pintype "bidirectional"))
    )
    (net (code "12") (name "B14_L8_N") (class "Default")
      (node (ref "JM2") (pin "62") (pinfunction "62_62") (pintype "bidirectional"))
    )
    (net (code "13") (name "B14_L8_P") (class "Default")
      (node (ref "JM2") (pin "60") (pinfunction "60_60") (pintype "bidirectional"))
    )
    (net (code "14") (name "B14_L9_N") (class "Default")
      (node (ref "JM2") (pin "66") (pinfunction "66_66") (pintype "bidirectional"))
    )
    (net (code "15") (name "B14_L9_P") (class "Default")
      (node (ref "JM2") (pin "64") (pinfunction "64_64") (pintype "bidirectional"))
    )
    (net (code "16") (name "B14_L10_N") (class "Default")
      (node (ref "JM2") (pin "77") (pinfunction "77_77") (pintype "bidirectional"))
    )
    (net (code "17") (name "B14_L10_P") (class "Default")
      (node (ref "JM2") (pin "75") (pinfunction "75_75") (pintype "bidirectional"))
    )
    (net (code "18") (name "B14_L11_N") (class "Default")
      (node (ref "JM2") (pin "74") (pinfunction "74_74") (pintype "bidirectional"))
    )
    (net (code "19") (name "B14_L11_P") (class "Default")
      (node (ref "JM2") (pin "76") (pinfunction "76_76") (pintype "bidirectional"))
    )
    (net (code "20") (name "B14_L12_N") (class "Default")
      (node (ref "JM2") (pin "84") (pinfunction "84_84") (pintype "bidirectional"))
    )
    (net (code "21") (name "B14_L12_P") (class "Default")
      (node (ref "JM2") (pin "82") (pinfunction "82_82") (pintype "bidirectional"))
    )
    (net (code "22") (name "B14_L13_N") (class "Default")
      (node (ref "JM2") (pin "86") (pinfunction "86_86") (pintype "bidirectional"))
    )
    (net (code "23") (name "B14_L13_P") (class "Default")
      (node (ref "JM2") (pin "88") (pinfunction "88_88") (pintype "bidirectional"))
    )
    (net (code "24") (name "B14_L14_N") (class "Default")
      (node (ref "JM2") (pin "78") (pinfunction "78_78") (pintype "bidirectional"))
    )
    (net (code "25") (name "B14_L14_P") (class "Default")
      (node (ref "JM2") (pin "80") (pinfunction "80_80") (pintype "bidirectional"))
    )
    (net (code "26") (name "B14_L15_N") (class "Default")
      (node (ref "JM2") (pin "65") (pinfunction "65_65") (pintype "bidirectional"))
    )
    (net (code "27") (name "B14_L15_P") (class "Default")
      (node (ref "JM2") (pin "63") (pinfunction "63_63") (pintype "bidirectional"))
    )
    (net (code "28") (name "B14_L16_N") (class "Default")
      (node (ref "JM2") (pin "81") (pinfunction "81_81") (pintype "bidirectional"))
    )
    (net (code "29") (name "B14_L16_P") (class "Default")
      (node (ref "JM2") (pin "79") (pinfunction "79_79") (pintype "bidirectional"))
    )
    (net (code "30") (name "B14_L17_N") (class "Default")
      (node (ref "JM2") (pin "89") (pinfunction "89_89") (pintype "bidirectional"))
      (node (ref "PCIE-SOUTH") (pin "B9") (pinfunction "IO5_B9") (pintype "passive"))
    )
    (net (code "31") (name "B14_L17_P") (class "Default")
      (node (ref "JM2") (pin "91") (pinfunction "91_91") (pintype "bidirectional"))
      (node (ref "PCIE-SOUTH") (pin "B8") (pinfunction "IO4_B8") (pintype "passive"))
    )
    (net (code "32") (name "B14_L18_N") (class "Default")
      (node (ref "JM2") (pin "85") (pinfunction "85_85") (pintype "bidirectional"))
      (node (ref "PCIE-SOUTH") (pin "B11") (pinfunction "IO7_B11") (pintype "passive"))
    )
    (net (code "33") (name "B14_L18_P") (class "Default")
      (node (ref "JM2") (pin "87") (pinfunction "87_87") (pintype "bidirectional"))
      (node (ref "PCIE-SOUTH") (pin "B10") (pinfunction "IO6_B10") (pintype "passive"))
    )
    (net (code "34") (name "B14_L19_N") (class "Default")
      (node (ref "JM2") (pin "94") (pinfunction "94_94") (pintype "bidirectional"))
    )
    (net (code "35") (name "B14_L19_P") (class "Default")
      (node (ref "JM2") (pin "92") (pinfunction "92_92") (pintype "bidirectional"))
    )
    (net (code "36") (name "B14_L20_N") (class "Default")
      (node (ref "JM2") (pin "95") (pinfunction "95_95") (pintype "bidirectional"))
      (node (ref "PCIE-SOUTH") (pin "B6") (pinfunction "IO2_B6") (pintype "passive"))
    )
    (net (code "37") (name "B14_L20_P") (class "Default")
      (node (ref "JM2") (pin "93") (pinfunction "93_93") (pintype "bidirectional"))
      (node (ref "PCIE-SOUTH") (pin "B7") (pinfunction "IO3_B7") (pintype "passive"))
    )
    (net (code "38") (name "B14_L21_N") (class "Default")
      (node (ref "JM1") (pin "95") (pinfunction "95_95") (pintype "bidirectional"))
      (node (ref "U5") (pin "1") (pinfunction "EN_1") (pintype "input"))
    )
    (net (code "39") (name "B14_L21_P") (class "Default")
      (node (ref "JM1") (pin "93") (pinfunction "93_93") (pintype "bidirectional"))
    )
    (net (code "40") (name "B14_L22_N") (class "Default")
      (node (ref "JM2") (pin "96") (pinfunction "96_96") (pintype "bidirectional"))
    )
    (net (code "41") (name "B14_L22_P") (class "Default")
      (node (ref "JM2") (pin "98") (pinfunction "98_98") (pintype "bidirectional"))
    )
    (net (code "42") (name "B14_L23_N") (class "Default")
      (node (ref "JM1") (pin "89") (pinfunction "89_89") (pintype "bidirectional"))
    )
    (net (code "43") (name "B14_L23_P") (class "Default")
      (node (ref "JM1") (pin "91") (pinfunction "91_91") (pintype "bidirectional"))
    )
    (net (code "44") (name "B14_L24_N") (class "Default")
      (node (ref "JM1") (pin "85") (pinfunction "85_85") (pintype "bidirectional"))
    )
    (net (code "45") (name "B14_L24_P") (class "Default")
      (node (ref "JM1") (pin "87") (pinfunction "87_87") (pintype "bidirectional"))
    )
    (net (code "46") (name "B14_L25") (class "Default")
      (node (ref "JM2") (pin "97") (pinfunction "97_97") (pintype "bidirectional"))
      (node (ref "PCIE-SOUTH") (pin "B5") (pinfunction "IO1_B5") (pintype "passive"))
    )
    (net (code "47") (name "B15_L1_N") (class "Default")
      (node (ref "JM2") (pin "14") (pinfunction "14_14") (pintype "bidirectional"))
      (node (ref "PCIE-NORTH") (pin "A14") (pinfunction "LVDS_3B_A14") (pintype "passive"))
    )
    (net (code "48") (name "B15_L1_P") (class "Default")
      (node (ref "JM2") (pin "16") (pinfunction "16_16") (pintype "bidirectional"))
      (node (ref "PCIE-NORTH") (pin "A13") (pinfunction "LVDS_3A_A13") (pintype "passive"))
    )
    (net (code "49") (name "B15_L2_N") (class "Default")
      (node (ref "JM2") (pin "20") (pinfunction "20_20") (pintype "bidirectional"))
    )
    (net (code "50") (name "B15_L2_P") (class "Default")
      (node (ref "JM2") (pin "22") (pinfunction "22_22") (pintype "bidirectional"))
    )
    (net (code "51") (name "B15_L3_N") (class "Default")
      (node (ref "JM2") (pin "4") (pinfunction "4_4") (pintype "bidirectional"))
    )
    (net (code "52") (name "B15_L3_P") (class "Default")
      (node (ref "JM2") (pin "2") (pinfunction "2_2") (pintype "bidirectional"))
    )
    (net (code "53") (name "B15_L4_N") (class "Default")
      (node (ref "JM2") (pin "10") (pinfunction "10_10") (pintype "bidirectional"))
    )
    (net (code "54") (name "B15_L4_P") (class "Default")
      (node (ref "JM2") (pin "12") (pinfunction "12_12") (pintype "bidirectional"))
    )
    (net (code "55") (name "B15_L5_N") (class "Default")
      (node (ref "JM2") (pin "8") (pinfunction "8_8") (pintype "bidirectional"))
      (node (ref "PCIE-NORTH") (pin "A16") (pinfunction "LVDS_4A_A16") (pintype "passive"))
    )
    (net (code "56") (name "B15_L5_P") (class "Default")
      (node (ref "JM2") (pin "6") (pinfunction "6_6") (pintype "bidirectional"))
      (node (ref "PCIE-NORTH") (pin "A17") (pinfunction "LVDS_4B_A17") (pintype "passive"))
    )
    (net (code "57") (name "B15_L6_N") (class "Default")
      (node (ref "JM2") (pin "26") (pinfunction "26_26") (pintype "bidirectional"))
      (node (ref "PCIE-NORTH") (pin "A5") (pinfunction "LVDS_1A_A5") (pintype "passive"))
    )
    (net (code "58") (name "B15_L6_P") (class "Default")
      (node (ref "JM2") (pin "24") (pinfunction "24_24") (pintype "bidirectional"))
      (node (ref "PCIE-NORTH") (pin "A6") (pinfunction "LVDS_1B_A6") (pintype "passive"))
    )
    (net (code "59") (name "B15_L7_N") (class "Default")
      (node (ref "JM2") (pin "1") (pinfunction "1_1") (pintype "bidirectional"))
      (node (ref "PCIE-NORTH") (pin "B17") (pinfunction "LVDS_5B_B17") (pintype "passive"))
    )
    (net (code "60") (name "B15_L7_P") (class "Default")
      (node (ref "JM2") (pin "3") (pinfunction "3_3") (pintype "bidirectional"))
      (node (ref "PCIE-NORTH") (pin "B16") (pinfunction "LVDS_5A_B16") (pintype "passive"))
    )
    (net (code "61") (name "B15_L8_N") (class "Default")
      (node (ref "JM2") (pin "7") (pinfunction "7_7") (pintype "bidirectional"))
    )
    (net (code "62") (name "B15_L8_P") (class "Default")
      (node (ref "JM2") (pin "5") (pinfunction "5_5") (pintype "bidirectional"))
    )
    (net (code "63") (name "B15_L9_N") (class "Default")
      (node (ref "JM2") (pin "15") (pinfunction "15_15") (pintype "bidirectional"))
    )
    (net (code "64") (name "B15_L9_P") (class "Default")
      (node (ref "JM2") (pin "13") (pinfunction "13_13") (pintype "bidirectional"))
    )
    (net (code "65") (name "B15_L10_N") (class "Default")
      (node (ref "JM2") (pin "11") (pinfunction "11_11") (pintype "bidirectional"))
      (node (ref "PCIE-NORTH") (pin "A8") (pinfunction "LVDS_2A_A8") (pintype "passive"))
    )
    (net (code "66") (name "B15_L10_P") (class "Default")
      (node (ref "JM2") (pin "9") (pinfunction "9_9") (pintype "bidirectional"))
      (node (ref "PCIE-NORTH") (pin "A9") (pinfunction "LVDS_2B_A9") (pintype "passive"))
    )
    (net (code "67") (name "B15_L11_N") (class "Default")
      (node (ref "JM2") (pin "30") (pinfunction "30_30") (pintype "bidirectional"))
    )
    (net (code "68") (name "B15_L11_P") (class "Default")
      (node (ref "JM2") (pin "28") (pinfunction "28_28") (pintype "bidirectional"))
    )
    (net (code "69") (name "B15_L12_N") (class "Default")
      (node (ref "JM2") (pin "34") (pinfunction "34_34") (pintype "bidirectional"))
      (node (ref "PCIE-SOUTH") (pin "A8") (pinfunction "LVDS_2A_A8") (pintype "passive"))
    )
    (net (code "70") (name "B15_L12_P") (class "Default")
      (node (ref "JM2") (pin "32") (pinfunction "32_32") (pintype "bidirectional"))
      (node (ref "PCIE-SOUTH") (pin "A9") (pinfunction "LVDS_2B_A9") (pintype "passive"))
    )
    (net (code "71") (name "B15_L13_N") (class "Default")
      (node (ref "JM2") (pin "38") (pinfunction "38_38") (pintype "bidirectional"))
      (node (ref "PCIE-SOUTH") (pin "A6") (pinfunction "LVDS_1B_A6") (pintype "passive"))
    )
    (net (code "72") (name "B15_L13_P") (class "Default")
      (node (ref "JM2") (pin "40") (pinfunction "40_40") (pintype "bidirectional"))
      (node (ref "PCIE-SOUTH") (pin "A5") (pinfunction "LVDS_1A_A5") (pintype "passive"))
    )
    (net (code "73") (name "B15_L14_N") (class "Default")
      (node (ref "JM2") (pin "42") (pinfunction "42_42") (pintype "bidirectional"))
    )
    (net (code "74") (name "B15_L14_P") (class "Default")
      (node (ref "JM2") (pin "44") (pinfunction "44_44") (pintype "bidirectional"))
    )
    (net (code "75") (name "B15_L15_N") (class "Default")
      (node (ref "JM2") (pin "19") (pinfunction "19_19") (pintype "bidirectional"))
      (node (ref "PCIE-NORTH") (pin "A3") (pinfunction "LVDS_0B_A3") (pintype "passive"))
    )
    (net (code "76") (name "B15_L15_P") (class "Default")
      (node (ref "JM2") (pin "21") (pinfunction "21_21") (pintype "bidirectional"))
      (node (ref "PCIE-NORTH") (pin "A2") (pinfunction "LVDS_0A_A2") (pintype "passive"))
    )
    (net (code "77") (name "B15_L16_N") (class "Default")
      (node (ref "JM2") (pin "23") (pinfunction "23_23") (pintype "bidirectional"))
    )
    (net (code "78") (name "B15_L16_P") (class "Default")
      (node (ref "JM2") (pin "25") (pinfunction "25_25") (pintype "bidirectional"))
    )
    (net (code "79") (name "B15_L17_N") (class "Default")
      (node (ref "JM2") (pin "31") (pinfunction "31_31") (pintype "bidirectional"))
    )
    (net (code "80") (name "B15_L17_P") (class "Default")
      (node (ref "JM2") (pin "33") (pinfunction "33_33") (pintype "bidirectional"))
    )
    (net (code "81") (name "B15_L18_N") (class "Default")
      (node (ref "JM2") (pin "27") (pinfunction "27_27") (pintype "bidirectional"))
      (node (ref "PCIE-SOUTH") (pin "A17") (pinfunction "LVDS_4B_A17") (pintype "passive"))
    )
    (net (code "82") (name "B15_L18_P") (class "Default")
      (node (ref "JM2") (pin "29") (pinfunction "29_29") (pintype "bidirectional"))
      (node (ref "PCIE-SOUTH") (pin "A16") (pinfunction "LVDS_4A_A16") (pintype "passive"))
    )
    (net (code "83") (name "B15_L19_N") (class "Default")
      (node (ref "JM2") (pin "41") (pinfunction "41_41") (pintype "bidirectional"))
      (node (ref "PCIE-SOUTH") (pin "B17") (pinfunction "LVDS_5B_B17") (pintype "passive"))
    )
    (net (code "84") (name "B15_L19_P") (class "Default")
      (node (ref "JM2") (pin "43") (pinfunction "43_43") (pintype "bidirectional"))
      (node (ref "PCIE-SOUTH") (pin "B16") (pinfunction "LVDS_5A_B16") (pintype "passive"))
    )
    (net (code "85") (name "B15_L20_N") (class "Default")
      (node (ref "JM2") (pin "50") (pinfunction "50_50") (pintype "bidirectional"))
    )
    (net (code "86") (name "B15_L20_P") (class "Default")
      (node (ref "JM2") (pin "52") (pinfunction "52_52") (pintype "bidirectional"))
    )
    (net (code "87") (name "B15_L21_N") (class "Default")
      (node (ref "JM2") (pin "45") (pinfunction "45_45") (pintype "bidirectional"))
    )
    (net (code "88") (name "B15_L21_P") (class "Default")
      (node (ref "JM2") (pin "47") (pinfunction "47_47") (pintype "bidirectional"))
    )
    (net (code "89") (name "B15_L22_N") (class "Default")
      (node (ref "JM2") (pin "46") (pinfunction "46_46") (pintype "bidirectional"))
      (node (ref "PCIE-SOUTH") (pin "A3") (pinfunction "LVDS_0B_A3") (pintype "passive"))
    )
    (net (code "90") (name "B15_L22_P") (class "Default")
      (node (ref "JM2") (pin "48") (pinfunction "48_48") (pintype "bidirectional"))
      (node (ref "PCIE-SOUTH") (pin "A2") (pinfunction "LVDS_0A_A2") (pintype "passive"))
    )
    (net (code "91") (name "B15_L23_N") (class "Default")
      (node (ref "JM2") (pin "51") (pinfunction "51_51") (pintype "bidirectional"))
      (node (ref "PCIE-SOUTH") (pin "A13") (pinfunction "LVDS_3A_A13") (pintype "passive"))
    )
    (net (code "92") (name "B15_L23_P") (class "Default")
      (node (ref "JM2") (pin "49") (pinfunction "49_49") (pintype "bidirectional"))
      (node (ref "PCIE-SOUTH") (pin "A14") (pinfunction "LVDS_3B_A14") (pintype "passive"))
    )
    (net (code "93") (name "B15_L24_N") (class "Default")
      (node (ref "JM2") (pin "37") (pinfunction "37_37") (pintype "bidirectional"))
    )
    (net (code "94") (name "B15_L24_P") (class "Default")
      (node (ref "JM2") (pin "39") (pinfunction "39_39") (pintype "bidirectional"))
    )
    (net (code "95") (name "B34_L1_N") (class "Default")
      (node (ref "JM1") (pin "37") (pinfunction "37_37") (pintype "bidirectional"))
    )
    (net (code "96") (name "B34_L1_P") (class "Default")
      (node (ref "JM1") (pin "35") (pinfunction "35_35") (pintype "bidirectional"))
    )
    (net (code "97") (name "B34_L2_N") (class "Default")
      (node (ref "JM1") (pin "33") (pinfunction "33_33") (pintype "bidirectional"))
    )
    (net (code "98") (name "B34_L2_P") (class "Default")
      (node (ref "JM1") (pin "31") (pinfunction "31_31") (pintype "bidirectional"))
    )
    (net (code "99") (name "B34_L3_N") (class "Default")
      (node (ref "JM1") (pin "42") (pinfunction "42_42") (pintype "bidirectional"))
      (node (ref "U3") (pin "13") (pinfunction "SCLK_13") (pintype "input"))
    )
    (net (code "100") (name "B34_L3_P") (class "Default")
      (node (ref "JM1") (pin "40") (pinfunction "40_40") (pintype "bidirectional"))
      (node (ref "U3") (pin "17") (pinfunction "GPIO0_17") (pintype "bidirectional"))
    )
    (net (code "101") (name "B34_L4_N") (class "Default")
      (node (ref "JM1") (pin "41") (pinfunction "41_41") (pintype "bidirectional"))
      (node (ref "U3") (pin "12") (pinfunction "SDOUT_12") (pintype "output"))
    )
    (net (code "102") (name "B34_L4_P") (class "Default")
      (node (ref "JM1") (pin "39") (pinfunction "39_39") (pintype "bidirectional"))
    )
    (net (code "103") (name "B34_L5_N") (class "Default")
      (node (ref "JM1") (pin "45") (pinfunction "45_45") (pintype "bidirectional"))
      (node (ref "U3") (pin "10") (pinfunction "~{CS}_10") (pintype "input"))
    )
    (net (code "104") (name "B34_L5_P") (class "Default")
      (node (ref "JM1") (pin "43") (pinfunction "43_43") (pintype "bidirectional"))
      (node (ref "U3") (pin "11") (pinfunction "SDIN_11") (pintype "input"))
    )
    (net (code "105") (name "B34_L6_N") (class "Default")
      (node (ref "JM1") (pin "34") (pinfunction "34_34") (pintype "bidirectional"))
    )
    (net (code "106") (name "B34_L6_P") (class "Default")
      (node (ref "JM1") (pin "32") (pinfunction "32_32") (pintype "bidirectional"))
    )
    (net (code "107") (name "B34_L7_N") (class "Default")
      (node (ref "JM1") (pin "38") (pinfunction "38_38") (pintype "bidirectional"))
      (node (ref "U3") (pin "18") (pinfunction "GPIO1_18") (pintype "bidirectional"))
    )
    (net (code "108") (name "B34_L7_P") (class "Default")
      (node (ref "JM1") (pin "36") (pinfunction "36_36") (pintype "bidirectional"))
    )
    (net (code "109") (name "B34_L8_N") (class "Default")
      (node (ref "JM1") (pin "52") (pinfunction "52_52") (pintype "bidirectional"))
      (node (ref "U2") (pin "13") (pinfunction "SCLK_13") (pintype "input"))
    )
    (net (code "110") (name "B34_L8_P") (class "Default")
      (node (ref "JM1") (pin "50") (pinfunction "50_50") (pintype "bidirectional"))
      (node (ref "U2") (pin "12") (pinfunction "SDOUT_12") (pintype "output"))
    )
    (net (code "111") (name "B34_L9_N") (class "Default")
      (node (ref "JM1") (pin "46") (pinfunction "46_46") (pintype "bidirectional"))
      (node (ref "U3") (pin "33") (pinfunction "GPIO2_33") (pintype "bidirectional"))
    )
    (net (code "112") (name "B34_L9_P") (class "Default")
      (node (ref "JM1") (pin "44") (pinfunction "44_44") (pintype "bidirectional"))
      (node (ref "U3") (pin "36") (pinfunction "GPIO3_36") (pintype "bidirectional"))
    )
    (net (code "113") (name "B34_L10_N") (class "Default")
      (node (ref "JM1") (pin "51") (pinfunction "51_51") (pintype "bidirectional"))
      (node (ref "U4") (pin "11") (pinfunction "SDIN_11") (pintype "input"))
    )
    (net (code "114") (name "B34_L10_P") (class "Default")
      (node (ref "JM1") (pin "49") (pinfunction "49_49") (pintype "bidirectional"))
      (node (ref "U4") (pin "10") (pinfunction "~{CS}_10") (pintype "input"))
    )
    (net (code "115") (name "B34_L11_N") (class "Default")
      (node (ref "JM1") (pin "53") (pinfunction "53_53") (pintype "bidirectional"))
      (node (ref "U4") (pin "12") (pinfunction "SDOUT_12") (pintype "output"))
    )
    (net (code "116") (name "B34_L11_P") (class "Default")
      (node (ref "JM1") (pin "55") (pinfunction "55_55") (pintype "bidirectional"))
      (node (ref "U4") (pin "17") (pinfunction "GPIO0_17") (pintype "bidirectional"))
    )
    (net (code "117") (name "B34_L12_N") (class "Default")
      (node (ref "JM1") (pin "57") (pinfunction "57_57") (pintype "bidirectional"))
      (node (ref "U4") (pin "18") (pinfunction "GPIO1_18") (pintype "bidirectional"))
    )
    (net (code "118") (name "B34_L12_P") (class "Default")
      (node (ref "JM1") (pin "59") (pinfunction "59_59") (pintype "bidirectional"))
      (node (ref "U2") (pin "11") (pinfunction "SDIN_11") (pintype "input"))
    )
    (net (code "119") (name "B34_L13_N") (class "Default")
      (node (ref "JM1") (pin "56") (pinfunction "56_56") (pintype "bidirectional"))
      (node (ref "U2") (pin "18") (pinfunction "GPIO1_18") (pintype "bidirectional"))
    )
    (net (code "120") (name "B34_L13_P") (class "Default")
      (node (ref "JM1") (pin "54") (pinfunction "54_54") (pintype "bidirectional"))
      (node (ref "U2") (pin "17") (pinfunction "GPIO0_17") (pintype "bidirectional"))
    )
    (net (code "121") (name "B34_L14_N") (class "Default")
      (node (ref "JM1") (pin "60") (pinfunction "60_60") (pintype "bidirectional"))
      (node (ref "U2") (pin "36") (pinfunction "GPIO3_36") (pintype "bidirectional"))
    )
    (net (code "122") (name "B34_L14_P") (class "Default")
      (node (ref "JM1") (pin "58") (pinfunction "58_58") (pintype "bidirectional"))
      (node (ref "U2") (pin "33") (pinfunction "GPIO2_33") (pintype "bidirectional"))
    )
    (net (code "123") (name "B34_L15_N") (class "Default")
      (node (ref "JM1") (pin "62") (pinfunction "62_62") (pintype "bidirectional"))
    )
    (net (code "124") (name "B34_L15_P") (class "Default")
      (node (ref "JM1") (pin "64") (pinfunction "64_64") (pintype "bidirectional"))
    )
    (net (code "125") (name "B34_L16_N") (class "Default")
      (node (ref "JM1") (pin "68") (pinfunction "68_68") (pintype "bidirectional"))
    )
    (net (code "126") (name "B34_L16_P") (class "Default")
      (node (ref "JM1") (pin "70") (pinfunction "70_70") (pintype "bidirectional"))
    )
    (net (code "127") (name "B34_L17_N") (class "Default")
      (node (ref "JM1") (pin "63") (pinfunction "63_63") (pintype "bidirectional"))
      (node (ref "U2") (pin "10") (pinfunction "~{CS}_10") (pintype "input"))
    )
    (net (code "128") (name "B34_L17_P") (class "Default")
      (node (ref "JM1") (pin "65") (pinfunction "65_65") (pintype "bidirectional"))
      (node (ref "U4") (pin "36") (pinfunction "GPIO3_36") (pintype "bidirectional"))
    )
    (net (code "129") (name "B34_L18_N") (class "Default")
      (node (ref "JM1") (pin "74") (pinfunction "74_74") (pintype "bidirectional"))
    )
    (net (code "130") (name "B34_L18_P") (class "Default")
      (node (ref "JM1") (pin "72") (pinfunction "72_72") (pintype "bidirectional"))
    )
    (net (code "131") (name "B34_L19_N") (class "Default")
      (node (ref "JM1") (pin "71") (pinfunction "71_71") (pintype "bidirectional"))
    )
    (net (code "132") (name "B34_L19_P") (class "Default")
      (node (ref "JM1") (pin "73") (pinfunction "73_73") (pintype "bidirectional"))
    )
    (net (code "133") (name "B34_L20_N") (class "Default")
      (node (ref "JM1") (pin "76") (pinfunction "76_76") (pintype "bidirectional"))
      (node (ref "R4") (pin "1") (pinfunction "1_1") (pintype "passive"))
    )
    (net (code "134") (name "B34_L20_P") (class "Default")
      (node (ref "JM1") (pin "78") (pinfunction "78_78") (pintype "bidirectional"))
      (node (ref "R5") (pin "1") (pinfunction "1_1") (pintype "passive"))
    )
    (net (code "135") (name "B34_L21_N") (class "Default")
      (node (ref "JM1") (pin "69") (pinfunction "69_69") (pintype "bidirectional"))
    )
    (net (code "136") (name "B34_L21_P") (class "Default")
      (node (ref "JM1") (pin "67") (pinfunction "67_67") (pintype "bidirectional"))
      (node (ref "U4") (pin "33") (pinfunction "GPIO2_33") (pintype "bidirectional"))
    )
    (net (code "137") (name "B34_L22_N") (class "Default")
      (node (ref "JM1") (pin "75") (pinfunction "75_75") (pintype "bidirectional"))
    )
    (net (code "138") (name "B34_L22_P") (class "Default")
      (node (ref "JM1") (pin "77") (pinfunction "77_77") (pintype "bidirectional"))
    )
    (net (code "139") (name "B34_L23_N") (class "Default")
      (node (ref "JM1") (pin "79") (pinfunction "79_79") (pintype "bidirectional"))
    )
    (net (code "140") (name "B34_L23_P") (class "Default")
      (node (ref "JM1") (pin "81") (pinfunction "81_81") (pintype "bidirectional"))
    )
    (net (code "141") (name "B34_L24_N") (class "Default")
      (node (ref "JM1") (pin "80") (pinfunction "80_80") (pintype "bidirectional"))
      (node (ref "R6") (pin "1") (pinfunction "1_1") (pintype "passive"))
    )
    (net (code "142") (name "B34_L24_P") (class "Default")
      (node (ref "JM1") (pin "82") (pinfunction "82_82") (pintype "bidirectional"))
      (node (ref "R7") (pin "1") (pinfunction "1_1") (pintype "passive"))
    )
    (net (code "143") (name "BOOTMODE") (class "Default")
      (node (ref "JM2") (pin "100") (pinfunction "100_100") (pintype "bidirectional"))
      (node (ref "JP3") (pin "1") (pinfunction "1_1") (pintype "passive"))
    )
    (net (code "144") (name "DONE") (class "Default")
      (node (ref "D5") (pin "A") (pinfunction "A_A") (pintype "passive"))
      (node (ref "JM1") (pin "96") (pinfunction "96_96") (pintype "bidirectional"))
      (node (ref "R3") (pin "1") (pinfunction "1_1") (pintype "passive"))
    )
    (net (code "145") (name "EN_A") (class "Default")
      (node (ref "U6") (pin "1") (pinfunction "EN_1") (pintype "input"))
    )
    (net (code "146") (name "EN_B") (class "Default")
      (node (ref "U9") (pin "1") (pinfunction "EN_1") (pintype "input"))
    )
    (net (code "147") (name "FB_A") (class "Default")
      (node (ref "R17") (pin "2") (pinfunction "2_2") (pintype "passive"))
      (node (ref "R18") (pin "1") (pinfunction "1_1") (pintype "passive"))
      (node (ref "U6") (pin "7") (pinfunction "FB_7") (pintype "output"))
    )
    (net (code "148") (name "FB_B") (class "Default")
      (node (ref "R16") (pin "1") (pinfunction "1_1") (pintype "passive"))
      (node (ref "R19") (pin "2") (pinfunction "2_2") (pintype "passive"))
      (node (ref "U9") (pin "7") (pinfunction "FB_7") (pintype "output"))
    )
    (net (code "149") (name "GND") (class "Default")
      (node (ref "C1") (pin "2") (pinfunction "2_2") (pintype "passive"))
      (node (ref "C10") (pin "2") (pinfunction "2_2") (pintype "passive"))
      (node (ref "C11") (pin "2") (pinfunction "2_2") (pintype "passive"))
      (node (ref "C12") (pin "2") (pinfunction "2_2") (pintype "passive"))
      (node (ref "C13") (pin "2") (pinfunction "2_2") (pintype "passive"))
      (node (ref "C14") (pin "2") (pinfunction "2_2") (pintype "passive"))
      (node (ref "C15") (pin "2") (pinfunction "2_2") (pintype "passive"))
      (node (ref "C16") (pin "2") (pinfunction "2_2") (pintype "passive"))
      (node (ref "C22") (pin "2") (pinfunction "2_2") (pintype "passive"))
      (node (ref "C23") (pin "2") (pinfunction "2_2") (pintype "passive"))
      (node (ref "C24") (pin "2") (pinfunction "2_2") (pintype "passive"))
      (node (ref "C25") (pin "2") (pinfunction "2_2") (pintype "passive"))
      (node (ref "C26") (pin "2") (pinfunction "2_2") (pintype "passive"))
      (node (ref "C27") (pin "2") (pinfunction "2_2") (pintype "passive"))
      (node (ref "C28") (pin "2") (pinfunction "2_2") (pintype "passive"))
      (node (ref "C29") (pin "2") (pinfunction "2_2") (pintype "passive"))
      (node (ref "C30") (pin "2") (pinfunction "2_2") (pintype "passive"))
      (node (ref "C31") (pin "2") (pinfunction "2_2") (pintype "passive"))
      (node (ref "C32") (pin "2") (pinfunction "2_2") (pintype "passive"))
      (node (ref "C33") (pin "2") (pinfunction "2_2") (pintype "passive"))
      (node (ref "C34") (pin "2") (pinfunction "2_2") (pintype "passive"))
      (node (ref "C40") (pin "2") (pinfunction "2_2") (pintype "passive"))
      (node (ref "C41") (pin "2") (pinfunction "2_2") (pintype "passive"))
      (node (ref "C42") (pin "2") (pinfunction "2_2") (pintype "passive"))
      (node (ref "C43") (pin "2") (pinfunction "2_2") (pintype "passive"))
      (node (ref "C44") (pin "2") (pinfunction "2_2") (pintype "passive"))
      (node (ref "C45") (pin "2") (pinfunction "2_2") (pintype "passive"))
      (node (ref "C46") (pin "2") (pinfunction "2_2") (pintype "passive"))
      (node (ref "C47") (pin "2") (pinfunction "2_2") (pintype "passive"))
      (node (ref "C48") (pin "2") (pinfunction "2_2") (pintype "passive"))
      (node (ref "C49") (pin "2") (pinfunction "2_2") (pintype "passive"))
      (node (ref "C5") (pin "2") (pinfunction "2_2") (pintype "passive"))
      (node (ref "C50") (pin "2") (pinfunction "2_2") (pintype "passive"))
      (node (ref "C51") (pin "2") (pinfunction "2_2") (pintype "passive"))
      (node (ref "C52") (pin "2") (pinfunction "2_2") (pintype "passive"))
      (node (ref "C53") (pin "2") (pinfunction "2_2") (pintype "passive"))
      (node (ref "C56") (pin "2") (pinfunction "2_2") (pintype "passive"))
      (node (ref "C57") (pin "2") (pinfunction "2_2") (pintype "passive"))
      (node (ref "C58") (pin "2") (pinfunction "2_2") (pintype "passive"))
      (node (ref "C59") (pin "2") (pinfunction "2_2") (pintype "passive"))
      (node (ref "C6") (pin "2") (pinfunction "2_2") (pintype "passive"))
      (node (ref "C7") (pin "2") (pinfunction "2_2") (pintype "passive"))
      (node (ref "C8") (pin "2") (pinfunction "2_2") (pintype "passive"))
      (node (ref "C9") (pin "2") (pinfunction "2_2") (pintype "passive"))
      (node (ref "D5") (pin "C") (pinfunction "C_C") (pintype "passive"))
      (node (ref "JM1") (pin "100") (pinfunction "100_100") (pintype "bidirectional"))
      (node (ref "JM1") (pin "11") (pinfunction "11_11") (pintype "bidirectional"))
      (node (ref "JM1") (pin "12") (pinfunction "12_12") (pintype "bidirectional"))
      (node (ref "JM1") (pin "17") (pinfunction "17_17") (pintype "bidirectional"))
      (node (ref "JM1") (pin "18") (pinfunction "18_18") (pintype "bidirectional"))
      (node (ref "JM1") (pin "23") (pinfunction "23_23") (pintype "bidirectional"))
      (node (ref "JM1") (pin "24") (pinfunction "24_24") (pintype "bidirectional"))
      (node (ref "JM1") (pin "29") (pinfunction "29_29") (pintype "bidirectional"))
      (node (ref "JM1") (pin "30") (pinfunction "30_30") (pintype "bidirectional"))
      (node (ref "JM1") (pin "47") (pinfunction "47_47") (pintype "bidirectional"))
      (node (ref "JM1") (pin "48") (pinfunction "48_48") (pintype "bidirectional"))
      (node (ref "JM1") (pin "5") (pinfunction "5_5") (pintype "bidirectional"))
      (node (ref "JM1") (pin "6") (pinfunction "6_6") (pintype "bidirectional"))
      (node (ref "JM1") (pin "66") (pinfunction "66_66") (pintype "bidirectional"))
      (node (ref "JM1") (pin "84") (pinfunction "84_84") (pintype "bidirectional"))
      (node (ref "JM1") (pin "98") (pinfunction "98_98") (pintype "bidirectional"))
      (node (ref "JM1") (pin "F1") (pinfunction "F1_F1") (pintype "bidirectional"))
      (node (ref "JM1") (pin "F2") (pinfunction "F2_F2") (pintype "bidirectional"))
      (node (ref "JM2") (pin "17") (pinfunction "17_17") (pintype "bidirectional"))
      (node (ref "JM2") (pin "35") (pinfunction "35_35") (pintype "bidirectional"))
      (node (ref "JM2") (pin "36") (pinfunction "36_36") (pintype "bidirectional"))
      (node (ref "JM2") (pin "72") (pinfunction "72_72") (pintype "bidirectional"))
      (node (ref "JM2") (pin "83") (pinfunction "83_83") (pintype "bidirectional"))
      (node (ref "JM2") (pin "90") (pinfunction "90_90") (pintype "bidirectional"))
      (node (ref "JM2") (pin "F1") (pinfunction "F1_F1") (pintype "bidirectional"))
      (node (ref "JM2") (pin "F2") (pinfunction "F2_F2") (pintype "bidirectional"))
      (node (ref "JP1") (pin "1") (pinfunction "1_1") (pintype "passive"))
      (node (ref "JP1") (pin "11") (pinfunction "11_11") (pintype "passive"))
      (node (ref "JP1") (pin "13") (pinfunction "13_13") (pintype "passive"))
      (node (ref "JP1") (pin "3") (pinfunction "3_3") (pintype "passive"))
      (node (ref "JP1") (pin "5") (pinfunction "5_5") (pintype "passive"))
      (node (ref "JP1") (pin "7") (pinfunction "7_7") (pintype "passive"))
      (node (ref "JP1") (pin "9") (pinfunction "9_9") (pintype "passive"))
      (node (ref "JP2") (pin "3") (pinfunction "3_3") (pintype "passive"))
      (node (ref "JP3") (pin "2") (pinfunction "2_2") (pintype "passive"))
      (node (ref "PCIE-NORTH") (pin "A1") (pinfunction "GND_A1") (pintype "passive"))
      (node (ref "PCIE-NORTH") (pin "A10") (pinfunction "GND_A10") (pintype "passive"))
      (node (ref "PCIE-NORTH") (pin "A12") (pinfunction "GND_A12") (pintype "passive"))
      (node (ref "PCIE-NORTH") (pin "A15") (pinfunction "GND_A15") (pintype "passive"))
      (node (ref "PCIE-NORTH") (pin "A18") (pinfunction "GND_A18") (pintype "passive"))
      (node (ref "PCIE-NORTH") (pin "A4") (pinfunction "GND_A4") (pintype "passive"))
      (node (ref "PCIE-NORTH") (pin "A7") (pinfunction "GND_A7") (pintype "passive"))
      (node (ref "PCIE-NORTH") (pin "B15") (pinfunction "GND_B15") (pintype "passive"))
      (node (ref "PCIE-NORTH") (pin "B18") (pinfunction "GND_B18") (pintype "passive"))
      (node (ref "PCIE-SOUTH") (pin "A1") (pinfunction "GND_A1") (pintype "passive"))
      (node (ref "PCIE-SOUTH") (pin "A10") (pinfunction "GND_A10") (pintype "passive"))
      (node (ref "PCIE-SOUTH") (pin "A12") (pinfunction "GND_A12") (pintype "passive"))
      (node (ref "PCIE-SOUTH") (pin "A15") (pinfunction "GND_A15") (pintype "passive"))
      (node (ref "PCIE-SOUTH") (pin "A18") (pinfunction "GND_A18") (pintype "passive"))
      (node (ref "PCIE-SOUTH") (pin "A4") (pinfunction "GND_A4") (pintype "passive"))
      (node (ref "PCIE-SOUTH") (pin "A7") (pinfunction "GND_A7") (pintype "passive"))
      (node (ref "PCIE-SOUTH") (pin "B15") (pinfunction "GND_B15") (pintype "passive"))
      (node (ref "PCIE-SOUTH") (pin "B18") (pinfunction "GND_B18") (pintype "passive"))
      (node (ref "R10") (pin "2") (pinfunction "2_2") (pintype "passive"))
      (node (ref "R11") (pin "2") (pinfunction "2_2") (pintype "passive"))
      (node (ref "R12") (pin "2") (pinfunction "2_2") (pintype "passive"))
      (node (ref "R13") (pin "2") (pinfunction "2_2") (pintype "passive"))
      (node (ref "R14") (pin "2") (pinfunction "2_2") (pintype "passive"))
      (node (ref "R17") (pin "1") (pinfunction "1_1") (pintype "passive"))
      (node (ref "R19") (pin "1") (pinfunction "1_1") (pintype "passive"))
      (node (ref "R2") (pin "2") (pinfunction "2_2") (pintype "passive"))
      (node (ref "R8") (pin "2") (pinfunction "2_2") (pintype "passive"))
      (node (ref "R9") (pin "2") (pinfunction "2_2") (pintype "passive"))
      (node (ref "U1") (pin "1") (pinfunction "A0_1") (pintype "input"))
      (node (ref "U1") (pin "2") (pinfunction "A1_2") (pintype "input"))
      (node (ref "U1") (pin "3") (pinfunction "A2_3") (pintype "input"))
      (node (ref "U1") (pin "4") (pinfunction "GND_4") (pintype "passive"))
      (node (ref "U1") (pin "EP") (pinfunction "EP_EP") (pintype "passive"))
      (node (ref "U2") (pin "1") (pinfunction "VEE_SDI_1") (pintype "power_in"))
      (node (ref "U2") (pin "14") (pinfunction "VSS_14") (pintype "power_in"))
      (node (ref "U2") (pin "15") (pinfunction "VSS_15") (pintype "power_in"))
      (node (ref "U2") (pin "19") (pinfunction "VEE_CORE_19") (pintype "power_in"))
      (node (ref "U2") (pin "21") (pinfunction "VEEO_21") (pintype "power_in"))
      (node (ref "U2") (pin "28") (pinfunction "VEEO_28") (pintype "power_in"))
      (node (ref "U2") (pin "31") (pinfunction "VEE_CORE_31") (pintype "power_in"))
      (node (ref "U2") (pin "37") (pinfunction "VEE_CORE_37") (pintype "power_in"))
      (node (ref "U2") (pin "38") (pinfunction "VEE_CORE_38") (pintype "power_in"))
      (node (ref "U2") (pin "8") (pinfunction "VEE_SDI_8") (pintype "power_in"))
      (node (ref "U3") (pin "1") (pinfunction "VEE_DDI_1") (pintype "power_in"))
      (node (ref "U3") (pin "14") (pinfunction "VSS_14") (pintype "power_in"))
      (node (ref "U3") (pin "15") (pinfunction "VSS_15") (pintype "power_in"))
      (node (ref "U3") (pin "19") (pinfunction "VEE_CORE_19") (pintype "power_in"))
      (node (ref "U3") (pin "21") (pinfunction "VEEO_21") (pintype "power_in"))
      (node (ref "U3") (pin "28") (pinfunction "VEEO_28") (pintype "power_in"))
      (node (ref "U3") (pin "31") (pinfunction "VEE_CORE_31") (pintype "power_in"))
      (node (ref "U3") (pin "37") (pinfunction "VEE_CORE_37") (pintype "power_in"))
      (node (ref "U3") (pin "38") (pinfunction "VEE_CORE_38") (pintype "power_in"))
      (node (ref "U3") (pin "8") (pinfunction "VEE_DDI_8") (pintype "power_in"))
      (node (ref "U4") (pin "1") (pinfunction "VEE_DDI_1") (pintype "power_in"))
      (node (ref "U4") (pin "14") (pinfunction "VSS_14") (pintype "power_in"))
      (node (ref "U4") (pin "15") (pinfunction "VSS_15") (pintype "power_in"))
      (node (ref "U4") (pin "19") (pinfunction "VEE_CORE_19") (pintype "power_in"))
      (node (ref "U4") (pin "21") (pinfunction "VEEO_21") (pintype "power_in"))
      (node (ref "U4") (pin "28") (pinfunction "VEEO_28") (pintype "power_in"))
      (node (ref "U4") (pin "31") (pinfunction "VEE_CORE_31") (pintype "power_in"))
      (node (ref "U4") (pin "37") (pinfunction "VEE_CORE_37") (pintype "power_in"))
      (node (ref "U4") (pin "38") (pinfunction "VEE_CORE_38") (pintype "power_in"))
      (node (ref "U4") (pin "8") (pinfunction "VEE_DDI_8") (pintype "power_in"))
      (node (ref "U5") (pin "3") (pinfunction "GND_3") (pintype "passive"))
      (node (ref "U6") (pin "5") (pinfunction "GND_5") (pintype "passive"))
      (node (ref "U6") (pin "6") (pinfunction "GND_6") (pintype "passive"))
      (node (ref "U6") (pin "EP") (pinfunction "GND_EP") (pintype "passive"))
      (node (ref "U9") (pin "5") (pinfunction "GND_5") (pintype "passive"))
      (node (ref "U9") (pin "6") (pinfunction "GND_6") (pintype "passive"))
      (node (ref "U9") (pin "EP") (pinfunction "GND_EP") (pintype "passive"))
      (node (ref "X1") (pin "2@1") (pinfunction "GND_2@1") (pintype "passive"))
      (node (ref "X1") (pin "2@2") (pinfunction "GND_2@2") (pintype "passive"))
      (node (ref "X1") (pin "2@3") (pinfunction "GND_2@3") (pintype "passive"))
      (node (ref "X2") (pin "2@1") (pinfunction "GND_2@1") (pintype "passive"))
      (node (ref "X2") (pin "2@2") (pinfunction "GND_2@2") (pintype "passive"))
      (node (ref "X2") (pin "2@3") (pinfunction "GND_2@3") (pintype "passive"))
      (node (ref "X3") (pin "2@1") (pinfunction "GND_2@1") (pintype "passive"))
      (node (ref "X3") (pin "2@2") (pinfunction "GND_2@2") (pintype "passive"))
      (node (ref "X3") (pin "2@3") (pinfunction "GND_2@3") (pintype "passive"))
    )
    (net (code "150") (name "I2C_V") (class "Default")
      (node (ref "C1") (pin "1") (pinfunction "1_1") (pintype "passive"))
      (node (ref "PCIE-NORTH") (pin "B3") (pinfunction "V_I2C_B3") (pintype "passive"))
      (node (ref "R1") (pin "1") (pinfunction "1_1") (pintype "passive"))
      (node (ref "U1") (pin "8") (pinfunction "VCC_8") (pintype "power_in"))
    )
    (net (code "151") (name "MGT_CLK0_N") (class "Default")
      (node (ref "C55") (pin "2") (pinfunction "2_2") (pintype "passive"))
      (node (ref "JM1") (pin "4") (pinfunction "4_4") (pintype "bidirectional"))
    )
    (net (code "152") (name "MGT_CLK0_P") (class "Default")
      (node (ref "C54") (pin "2") (pinfunction "2_2") (pintype "passive"))
      (node (ref "JM1") (pin "2") (pinfunction "2_2") (pintype "bidirectional"))
    )
    (net (code "153") (name "MGT_RX0_N") (class "Default")
      (node (ref "JM1") (pin "21") (pinfunction "21_21") (pintype "bidirectional"))
      (node (ref "U2") (pin "27") (pinfunction "DDO0_27") (pintype "output"))
    )
    (net (code "154") (name "MGT_RX0_P") (class "Default")
      (node (ref "JM1") (pin "19") (pinfunction "19_19") (pintype "bidirectional"))
      (node (ref "U2") (pin "26") (pinfunction "~{DDO0}_26") (pintype "output"))
    )
    (net (code "155") (name "MGT_RX1_N") (class "Default")
      (node (ref "JM1") (pin "15") (pinfunction "15_15") (pintype "bidirectional"))
      (node (ref "U2") (pin "23") (pinfunction "DDO1/RCO_23") (pintype "output"))
    )
    (net (code "156") (name "MGT_RX1_P") (class "Default")
      (node (ref "JM1") (pin "13") (pinfunction "13_13") (pintype "bidirectional"))
      (node (ref "U2") (pin "22") (pinfunction "~{DDO1}/~{RCO}_22") (pintype "output"))
    )
    (net (code "157") (name "MGT_RX2_N") (class "Default")
      (node (ref "JM1") (pin "9") (pinfunction "9_9") (pintype "bidirectional"))
    )
    (net (code "158") (name "MGT_RX2_P") (class "Default")
      (node (ref "JM1") (pin "7") (pinfunction "7_7") (pintype "bidirectional"))
    )
    (net (code "159") (name "MGT_RX3_N") (class "Default")
      (node (ref "JM1") (pin "3") (pinfunction "3_3") (pintype "bidirectional"))
    )
    (net (code "160") (name "MGT_RX3_P") (class "Default")
      (node (ref "JM1") (pin "1") (pinfunction "1_1") (pintype "bidirectional"))
    )
    (net (code "161") (name "MGT_TX0_N") (class "Default")
      (node (ref "JM1") (pin "28") (pinfunction "28_28") (pintype "bidirectional"))
      (node (ref "U4") (pin "6") (pinfunction "DDI_6") (pintype "input"))
    )
    (net (code "162") (name "MGT_TX0_P") (class "Default")
      (node (ref "JM1") (pin "26") (pinfunction "26_26") (pintype "bidirectional"))
      (node (ref "U4") (pin "7") (pinfunction "~{DDI}_7") (pintype "input"))
    )
    (net (code "163") (name "MGT_TX1_N") (class "Default")
      (node (ref "JM1") (pin "22") (pinfunction "22_22") (pintype "bidirectional"))
      (node (ref "U3") (pin "6") (pinfunction "DDI_6") (pintype "input"))
    )
    (net (code "164") (name "MGT_TX1_P") (class "Default")
      (node (ref "JM1") (pin "20") (pinfunction "20_20") (pintype "bidirectional"))
      (node (ref "U3") (pin "7") (pinfunction "~{DDI}_7") (pintype "input"))
    )
    (net (code "165") (name "MGT_TX2_N") (class "Default")
      (node (ref "JM1") (pin "16") (pinfunction "16_16") (pintype "bidirectional"))
    )
    (net (code "166") (name "MGT_TX2_P") (class "Default")
      (node (ref "JM1") (pin "14") (pinfunction "14_14") (pintype "bidirectional"))
    )
    (net (code "167") (name "MGT_TX3_N") (class "Default")
      (node (ref "JM1") (pin "10") (pinfunction "10_10") (pintype "bidirectional"))
    )
    (net (code "168") (name "MGT_TX3_P") (class "Default")
      (node (ref "JM1") (pin "8") (pinfunction "8_8") (pintype "bidirectional"))
    )
    (net (code "169") (name "N$34") (class "Default")
      (node (ref "U3") (pin "32") (pinfunction "RCLK_32") (pintype "input"))
    )
    (net (code "170") (name "N$81") (class "Default")
      (node (ref "U4") (pin "32") (pinfunction "RCLK_32") (pintype "input"))
    )
    (net (code "171") (name "N$83") (class "Default")
      (node (ref "U4") (pin "13") (pinfunction "SCLK_13") (pintype "input"))
    )
    (net (code "172") (name "N_5V") (class "Default")
      (node (ref "PCIE-NORTH") (pin "B12") (pinfunction "5V_B12") (pintype "passive"))
    )
    (net (code "173") (name "N_IO0") (class "Default")
      (node (ref "PCIE-NORTH") (pin "B4") (pinfunction "IO0_B4") (pintype "passive"))
    )
    (net (code "174") (name "N_IO1") (class "Default")
      (node (ref "PCIE-NORTH") (pin "B5") (pinfunction "IO1_B5") (pintype "passive"))
    )
    (net (code "175") (name "N_IO2") (class "Default")
      (node (ref "PCIE-NORTH") (pin "B6") (pinfunction "IO2_B6") (pintype "passive"))
    )
    (net (code "176") (name "N_IO3") (class "Default")
      (node (ref "PCIE-NORTH") (pin "B7") (pinfunction "IO3_B7") (pintype "passive"))
    )
    (net (code "177") (name "N_IO4") (class "Default")
      (node (ref "PCIE-NORTH") (pin "B8") (pinfunction "IO4_B8") (pintype "passive"))
    )
    (net (code "178") (name "N_IO5") (class "Default")
      (node (ref "PCIE-NORTH") (pin "B9") (pinfunction "IO5_B9") (pintype "passive"))
    )
    (net (code "179") (name "N_IO6") (class "Default")
      (node (ref "PCIE-NORTH") (pin "B10") (pinfunction "IO6_B10") (pintype "passive"))
    )
    (net (code "180") (name "N_IO7") (class "Default")
      (node (ref "PCIE-NORTH") (pin "B11") (pinfunction "IO7_B11") (pintype "passive"))
    )
    (net (code "181") (name "N_PCIE_V") (class "Default")
      (node (ref "PCIE-NORTH") (pin "B13") (pinfunction "VCC_B13") (pintype "passive"))
    )
    (net (code "182") (name "N_VCCIO") (class "Default")
      (node (ref "PCIE-NORTH") (pin "B14") (pinfunction "VCCIO_B14") (pintype "passive"))
    )
    (net (code "183") (name "Net-(C2-Pad1)") (class "Default")
      (node (ref "C2") (pin "1") (pinfunction "1_1") (pintype "passive"))
      (node (ref "X1") (pin "1") (pinfunction "1_1") (pintype "passive"))
    )
    (net (code "184") (name "Net-(C4-Pad2)") (class "Default")
      (node (ref "C4") (pin "2") (pinfunction "2_2") (pintype "passive"))
      (node (ref "R8") (pin "1") (pinfunction "1_1") (pintype "passive"))
    )
    (net (code "185") (name "Net-(C17-Pad2)") (class "Default")
      (node (ref "C17") (pin "2") (pinfunction "2_2") (pintype "passive"))
      (node (ref "X2") (pin "1") (pinfunction "1_1") (pintype "passive"))
    )
    (net (code "186") (name "Net-(C18-Pad2)") (class "Default")
      (node (ref "C18") (pin "2") (pinfunction "2_2") (pintype "passive"))
      (node (ref "R9") (pin "1") (pinfunction "1_1") (pintype "passive"))
    )
    (net (code "187") (name "Net-(C19-Pad2)") (class "Default")
      (node (ref "C19") (pin "2") (pinfunction "2_2") (pintype "passive"))
      (node (ref "R10") (pin "1") (pinfunction "1_1") (pintype "passive"))
    )
    (net (code "188") (name "Net-(C20-Pad2)") (class "Default")
      (node (ref "C20") (pin "2") (pinfunction "2_2") (pintype "passive"))
      (node (ref "R11") (pin "1") (pinfunction "1_1") (pintype "passive"))
    )
    (net (code "189") (name "Net-(C35-Pad2)") (class "Default")
      (node (ref "C35") (pin "2") (pinfunction "2_2") (pintype "passive"))
      (node (ref "X3") (pin "1") (pinfunction "1_1") (pintype "passive"))
    )
    (net (code "190") (name "Net-(C36-Pad2)") (class "Default")
      (node (ref "C36") (pin "2") (pinfunction "2_2") (pintype "passive"))
      (node (ref "R12") (pin "1") (pinfunction "1_1") (pintype "passive"))
    )
    (net (code "191") (name "Net-(C37-Pad2)") (class "Default")
      (node (ref "C37") (pin "2") (pinfunction "2_2") (pintype "passive"))
      (node (ref "R13") (pin "1") (pinfunction "1_1") (pintype "passive"))
    )
    (net (code "192") (name "Net-(C38-Pad2)") (class "Default")
      (node (ref "C38") (pin "2") (pinfunction "2_2") (pintype "passive"))
      (node (ref "R14") (pin "1") (pinfunction "1_1") (pintype "passive"))
    )
    (net (code "193") (name "Net-(D1-PadC)") (class "Default")
      (node (ref "D1") (pin "C") (pinfunction "C_C") (pintype "passive"))
      (node (ref "R4") (pin "2") (pinfunction "2_2") (pintype "passive"))
    )
    (net (code "194") (name "Net-(D2-PadC)") (class "Default")
      (node (ref "D2") (pin "C") (pinfunction "C_C") (pintype "passive"))
      (node (ref "R5") (pin "2") (pinfunction "2_2") (pintype "passive"))
    )
    (net (code "195") (name "Net-(D3-PadC)") (class "Default")
      (node (ref "D3") (pin "C") (pinfunction "C_C") (pintype "passive"))
      (node (ref "R6") (pin "2") (pinfunction "2_2") (pintype "passive"))
    )
    (net (code "196") (name "Net-(D4-PadC)") (class "Default")
      (node (ref "D4") (pin "C") (pinfunction "C_C") (pintype "passive"))
      (node (ref "R7") (pin "2") (pinfunction "2_2") (pintype "passive"))
    )
    (net (code "197") (name "Net-(U1-WP)") (class "Default")
      (node (ref "R1") (pin "2") (pinfunction "2_2") (pintype "passive"))
      (node (ref "R2") (pin "1") (pinfunction "1_1") (pintype "passive"))
      (node (ref "U1") (pin "7") (pinfunction "WP_7") (pintype "input"))
    )
    (net (code "198") (name "Net-(U2-LF+)") (class "Default")
      (node (ref "C3") (pin "1") (pinfunction "1_1") (pintype "passive"))
      (node (ref "U2") (pin "39") (pinfunction "LF+_39") (pintype "passive"))
    )
    (net (code "199") (name "Net-(U2-LF-)") (class "Default")
      (node (ref "C3") (pin "2") (pinfunction "2_2") (pintype "passive"))
      (node (ref "U2") (pin "40") (pinfunction "LF-_40") (pintype "passive"))
    )
    (net (code "200") (name "Net-(U2-SDI)") (class "Default")
      (node (ref "C2") (pin "2") (pinfunction "2_2") (pintype "passive"))
      (node (ref "U2") (pin "2") (pinfunction "SDI_2") (pintype "input"))
    )
    (net (code "201") (name "Net-(U2-SDI_TERM)") (class "Default")
      (node (ref "C4") (pin "1") (pinfunction "1_1") (pintype "passive"))
      (node (ref "U2") (pin "3") (pinfunction "SDI_TERM_3") (pintype "passive"))
    )
    (net (code "202") (name "Net-(U2-VCO_FILT)") (class "Default")
      (node (ref "C5") (pin "1") (pinfunction "1_1") (pintype "passive"))
      (node (ref "U2") (pin "34") (pinfunction "VCO_FILT_34") (pintype "passive"))
    )
    (net (code "203") (name "Net-(U2-VCO_FILT10)") (class "Default")
      (node (ref "C6") (pin "1") (pinfunction "1_1") (pintype "passive"))
      (node (ref "U2") (pin "30") (pinfunction "VCO_FILT10_30") (pintype "passive"))
    )
    (net (code "204") (name "Net-(U3-LF+)") (class "Default")
      (node (ref "C21") (pin "1") (pinfunction "1_1") (pintype "passive"))
      (node (ref "U3") (pin "39") (pinfunction "LF+_39") (pintype "passive"))
    )
    (net (code "205") (name "Net-(U3-LF-)") (class "Default")
      (node (ref "C21") (pin "2") (pinfunction "2_2") (pintype "passive"))
      (node (ref "U3") (pin "40") (pinfunction "LF-_40") (pintype "passive"))
    )
    (net (code "206") (name "Net-(U3-SDO0)") (class "Default")
      (node (ref "C17") (pin "1") (pinfunction "1_1") (pintype "passive"))
      (node (ref "U3") (pin "27") (pinfunction "SDO0_27") (pintype "output"))
    )
    (net (code "207") (name "Net-(U3-SDO1{slash}RCO)") (class "Default")
      (node (ref "C19") (pin "1") (pinfunction "1_1") (pintype "passive"))
      (node (ref "U3") (pin "23") (pinfunction "SDO1/RCO_23") (pintype "output"))
    )
    (net (code "208") (name "Net-(U3-TERM)") (class "Default")
      (node (ref "C22") (pin "1") (pinfunction "1_1") (pintype "passive"))
      (node (ref "U3") (pin "5") (pinfunction "TERM_5") (pintype "passive"))
    )
    (net (code "209") (name "Net-(U3-VCO_FILT)") (class "Default")
      (node (ref "C23") (pin "1") (pinfunction "1_1") (pintype "passive"))
      (node (ref "U3") (pin "34") (pinfunction "VCO_FILT_34") (pintype "passive"))
    )
    (net (code "210") (name "Net-(U3-VCO_FILT10)") (class "Default")
      (node (ref "C24") (pin "1") (pinfunction "1_1") (pintype "passive"))
      (node (ref "U3") (pin "30") (pinfunction "VCO_FILT10_30") (pintype "passive"))
    )
    (net (code "211") (name "Net-(U3-~{SDO0})") (class "Default")
      (node (ref "C20") (pin "1") (pinfunction "1_1") (pintype "passive"))
      (node (ref "U3") (pin "26") (pinfunction "~{SDO0}_26") (pintype "output"))
    )
    (net (code "212") (name "Net-(U3-~{SDO1}{slash}~{RCO})") (class "Default")
      (node (ref "C18") (pin "1") (pinfunction "1_1") (pintype "passive"))
      (node (ref "U3") (pin "22") (pinfunction "~{SDO1}/~{RCO}_22") (pintype "output"))
    )
    (net (code "213") (name "Net-(U4-LF+)") (class "Default")
      (node (ref "C39") (pin "1") (pinfunction "1_1") (pintype "passive"))
      (node (ref "U4") (pin "39") (pinfunction "LF+_39") (pintype "passive"))
    )
    (net (code "214") (name "Net-(U4-LF-)") (class "Default")
      (node (ref "C39") (pin "2") (pinfunction "2_2") (pintype "passive"))
      (node (ref "U4") (pin "40") (pinfunction "LF-_40") (pintype "passive"))
    )
    (net (code "215") (name "Net-(U4-SDO0)") (class "Default")
      (node (ref "C37") (pin "1") (pinfunction "1_1") (pintype "passive"))
      (node (ref "U4") (pin "27") (pinfunction "SDO0_27") (pintype "output"))
    )
    (net (code "216") (name "Net-(U4-SDO1{slash}RCO)") (class "Default")
      (node (ref "C35") (pin "1") (pinfunction "1_1") (pintype "passive"))
      (node (ref "U4") (pin "23") (pinfunction "SDO1/RCO_23") (pintype "output"))
    )
    (net (code "217") (name "Net-(U4-TERM)") (class "Default")
      (node (ref "C40") (pin "1") (pinfunction "1_1") (pintype "passive"))
      (node (ref "U4") (pin "5") (pinfunction "TERM_5") (pintype "passive"))
    )
    (net (code "218") (name "Net-(U4-VCO_FILT)") (class "Default")
      (node (ref "C41") (pin "1") (pinfunction "1_1") (pintype "passive"))
      (node (ref "U4") (pin "34") (pinfunction "VCO_FILT_34") (pintype "passive"))
    )
    (net (code "219") (name "Net-(U4-VCO_FILT10)") (class "Default")
      (node (ref "C42") (pin "1") (pinfunction "1_1") (pintype "passive"))
      (node (ref "U4") (pin "30") (pinfunction "VCO_FILT10_30") (pintype "passive"))
    )
    (net (code "220") (name "Net-(U4-~{SDO0})") (class "Default")
      (node (ref "C38") (pin "1") (pinfunction "1_1") (pintype "passive"))
      (node (ref "U4") (pin "26") (pinfunction "~{SDO0}_26") (pintype "output"))
    )
    (net (code "221") (name "Net-(U4-~{SDO1}{slash}~{RCO})") (class "Default")
      (node (ref "C36") (pin "1") (pinfunction "1_1") (pintype "passive"))
      (node (ref "U4") (pin "22") (pinfunction "~{SDO1}/~{RCO}_22") (pintype "output"))
    )
    (net (code "222") (name "Net-(U5-OUT+)") (class "Default")
      (node (ref "C54") (pin "1") (pinfunction "1_1") (pintype "passive"))
      (node (ref "R15") (pin "1") (pinfunction "1_1") (pintype "passive"))
      (node (ref "U5") (pin "4") (pinfunction "OUT+_4") (pintype "output"))
    )
    (net (code "223") (name "Net-(U5-OUT-)") (class "Default")
      (node (ref "C55") (pin "1") (pinfunction "1_1") (pintype "passive"))
      (node (ref "R15") (pin "2") (pinfunction "2_2") (pintype "passive"))
      (node (ref "U5") (pin "5") (pinfunction "OUT-_5") (pintype "output"))
    )
    (net (code "224") (name "PG_A") (class "Default")
      (node (ref "U6") (pin "2") (pinfunction "PG_2") (pintype "power_in"))
    )
    (net (code "225") (name "PG_B") (class "Default")
      (node (ref "U9") (pin "2") (pinfunction "PG_2") (pintype "power_in"))
    )
    (net (code "226") (name "PROG_B") (class "Default")
      (node (ref "JM1") (pin "94") (pinfunction "94_94") (pintype "bidirectional"))
    )
    (net (code "227") (name "SCL") (class "Default")
      (node (ref "PCIE-NORTH") (pin "B2") (pinfunction "SCL_B2") (pintype "passive"))
      (node (ref "U1") (pin "6") (pinfunction "SCL_6") (pintype "input"))
    )
    (net (code "228") (name "SDA") (class "Default")
      (node (ref "PCIE-NORTH") (pin "B1") (pinfunction "SDA_B1") (pintype "passive"))
      (node (ref "U1") (pin "5") (pinfunction "SDA_5") (pintype "bidirectional"))
    )
    (net (code "229") (name "SPI-CLK") (class "Default")
      (node (ref "JM2") (pin "67") (pinfunction "67_67") (pintype "bidirectional"))
    )
    (net (code "230") (name "SPI-CS") (class "Default")
      (node (ref "JM2") (pin "69") (pinfunction "69_69") (pintype "bidirectional"))
    )
    (net (code "231") (name "SPI-DQ0") (class "Default")
      (node (ref "JM2") (pin "68") (pinfunction "68_68") (pintype "bidirectional"))
    )
    (net (code "232") (name "SPI-DQ1") (class "Default")
      (node (ref "JM2") (pin "71") (pinfunction "71_71") (pintype "bidirectional"))
    )
    (net (code "233") (name "SPI-DQ2") (class "Default")
      (node (ref "JM2") (pin "73") (pinfunction "73_73") (pintype "bidirectional"))
    )
    (net (code "234") (name "SPI-DQ3") (class "Default")
      (node (ref "JM2") (pin "70") (pinfunction "70_70") (pintype "bidirectional"))
    )
    (net (code "235") (name "S_5V") (class "Default")
      (node (ref "JP2") (pin "1") (pinfunction "1_1") (pintype "passive"))
      (node (ref "PCIE-SOUTH") (pin "B12") (pinfunction "5V_B12") (pintype "passive"))
    )
    (net (code "236") (name "S_PCIE_V") (class "Default")
      (node (ref "PCIE-SOUTH") (pin "B13") (pinfunction "VCC_B13") (pintype "passive"))
    )
    (net (code "237") (name "S_VCCIO") (class "Default")
      (node (ref "PCIE-SOUTH") (pin "B14") (pinfunction "VCCIO_B14") (pintype "passive"))
    )
    (net (code "238") (name "TCK") (class "Default")
      (node (ref "JM1") (pin "90") (pinfunction "90_90") (pintype "bidirectional"))
      (node (ref "JP1") (pin "6") (pinfunction "6_6") (pintype "passive"))
    )
    (net (code "239") (name "TDI") (class "Default")
      (node (ref "JM1") (pin "86") (pinfunction "86_86") (pintype "bidirectional"))
      (node (ref "JP1") (pin "10") (pinfunction "10_10") (pintype "passive"))
    )
    (net (code "240") (name "TDO") (class "Default")
      (node (ref "JM1") (pin "88") (pinfunction "88_88") (pintype "bidirectional"))
      (node (ref "JP1") (pin "8") (pinfunction "8_8") (pintype "passive"))
    )
    (net (code "241") (name "TMS") (class "Default")
      (node (ref "JM1") (pin "92") (pinfunction "92_92") (pintype "bidirectional"))
      (node (ref "JP1") (pin "4") (pinfunction "4_4") (pintype "passive"))
    )
    (net (code "242") (name "VCCIO0") (class "Default")
      (node (ref "JM2") (pin "53") (pinfunction "53_53") (pintype "bidirectional"))
      (node (ref "JP1") (pin "2") (pinfunction "2_2") (pintype "passive"))
    )
    (net (code "243") (name "VCCIO14") (class "Default")
      (node (ref "JM1") (pin "83") (pinfunction "83_83") (pintype "bidirectional"))
    )
    (net (code "244") (name "VCCIO15") (class "Default")
      (node (ref "JM2") (pin "54") (pinfunction "54_54") (pintype "bidirectional"))
    )
    (net (code "245") (name "VCCIO34") (class "Default")
      (node (ref "JM1") (pin "61") (pinfunction "61_61") (pintype "bidirectional"))
    )
    (net (code "246") (name "VCCO_4") (class "Default")
      (node (ref "C14") (pin "1") (pinfunction "1_1") (pintype "passive"))
      (node (ref "C15") (pin "1") (pinfunction "1_1") (pintype "passive"))
      (node (ref "C16") (pin "1") (pinfunction "1_1") (pintype "passive"))
      (node (ref "FB3") (pin "2") (pinfunction "2_2") (pintype "passive"))
      (node (ref "U2") (pin "24") (pinfunction "VCCO_1_24") (pintype "power_in"))
      (node (ref "U2") (pin "25") (pinfunction "VCCO_0_25") (pintype "power_in"))
    )
    (net (code "247") (name "VCCO_8") (class "Default")
      (node (ref "C32") (pin "1") (pinfunction "1_1") (pintype "passive"))
      (node (ref "C33") (pin "1") (pinfunction "1_1") (pintype "passive"))
      (node (ref "C34") (pin "1") (pinfunction "1_1") (pintype "passive"))
      (node (ref "FB6") (pin "2") (pinfunction "2_2") (pintype "passive"))
      (node (ref "U3") (pin "24") (pinfunction "VCCO_1_24") (pintype "power_in"))
      (node (ref "U3") (pin "25") (pinfunction "VCCO_0_25") (pintype "power_in"))
    )
    (net (code "248") (name "VCCO_9") (class "Default")
      (node (ref "C50") (pin "1") (pinfunction "1_1") (pintype "passive"))
      (node (ref "C51") (pin "1") (pinfunction "1_1") (pintype "passive"))
      (node (ref "C52") (pin "1") (pinfunction "1_1") (pintype "passive"))
      (node (ref "FB9") (pin "2") (pinfunction "2_2") (pintype "passive"))
      (node (ref "U4") (pin "24") (pinfunction "VCCO_1_24") (pintype "power_in"))
      (node (ref "U4") (pin "25") (pinfunction "VCCO_0_25") (pintype "power_in"))
    )
    (net (code "249") (name "VCC_4") (class "Default")
      (node (ref "C11") (pin "1") (pinfunction "1_1") (pintype "passive"))
      (node (ref "C12") (pin "1") (pinfunction "1_1") (pintype "passive"))
      (node (ref "C13") (pin "1") (pinfunction "1_1") (pintype "passive"))
      (node (ref "FB2") (pin "2") (pinfunction "2_2") (pintype "passive"))
      (node (ref "U2") (pin "35") (pinfunction "VCC_CORE_35") (pintype "power_in"))
      (node (ref "U2") (pin "4") (pinfunction "VCC_SDI_4") (pintype "power_in"))
    )
    (net (code "250") (name "VCC_8") (class "Default")
      (node (ref "C29") (pin "1") (pinfunction "1_1") (pintype "passive"))
      (node (ref "C30") (pin "1") (pinfunction "1_1") (pintype "passive"))
      (node (ref "C31") (pin "1") (pinfunction "1_1") (pintype "passive"))
      (node (ref "FB5") (pin "2") (pinfunction "2_2") (pintype "passive"))
      (node (ref "U3") (pin "35") (pinfunction "VCC_CORE_35") (pintype "power_in"))
      (node (ref "U3") (pin "4") (pinfunction "VCC_DDI_4") (pintype "power_in"))
    )
    (net (code "251") (name "VCC_9") (class "Default")
      (node (ref "C47") (pin "1") (pinfunction "1_1") (pintype "passive"))
      (node (ref "C48") (pin "1") (pinfunction "1_1") (pintype "passive"))
      (node (ref "C49") (pin "1") (pinfunction "1_1") (pintype "passive"))
      (node (ref "FB8") (pin "2") (pinfunction "2_2") (pintype "passive"))
      (node (ref "U4") (pin "35") (pinfunction "VCC_CORE_35") (pintype "power_in"))
      (node (ref "U4") (pin "4") (pinfunction "VCC_DDI_4") (pintype "power_in"))
    )
    (net (code "252") (name "VDD_4") (class "Default")
      (node (ref "C10") (pin "1") (pinfunction "1_1") (pintype "passive"))
      (node (ref "C7") (pin "1") (pinfunction "1_1") (pintype "passive"))
      (node (ref "C8") (pin "1") (pinfunction "1_1") (pintype "passive"))
      (node (ref "C9") (pin "1") (pinfunction "1_1") (pintype "passive"))
      (node (ref "FB1") (pin "2") (pinfunction "2_2") (pintype "passive"))
      (node (ref "U2") (pin "16") (pinfunction "VDD_16") (pintype "power_in"))
      (node (ref "U2") (pin "20") (pinfunction "VCCO1V8_1_20") (pintype "power_in"))
      (node (ref "U2") (pin "29") (pinfunction "VCCO1V8_0_29") (pintype "power_in"))
    )
    (net (code "253") (name "VDD_8") (class "Default")
      (node (ref "C25") (pin "1") (pinfunction "1_1") (pintype "passive"))
      (node (ref "C26") (pin "1") (pinfunction "1_1") (pintype "passive"))
      (node (ref "C27") (pin "1") (pinfunction "1_1") (pintype "passive"))
      (node (ref "C28") (pin "1") (pinfunction "1_1") (pintype "passive"))
      (node (ref "FB4") (pin "2") (pinfunction "2_2") (pintype "passive"))
      (node (ref "U3") (pin "16") (pinfunction "VDD_16") (pintype "power_in"))
      (node (ref "U3") (pin "20") (pinfunction "VCCO1V8_1_20") (pintype "power_in"))
      (node (ref "U3") (pin "29") (pinfunction "VCCO1V8_0_29") (pintype "power_in"))
    )
    (net (code "254") (name "VDD_9") (class "Default")
      (node (ref "C43") (pin "1") (pinfunction "1_1") (pintype "passive"))
      (node (ref "C44") (pin "1") (pinfunction "1_1") (pintype "passive"))
      (node (ref "C45") (pin "1") (pinfunction "1_1") (pintype "passive"))
      (node (ref "C46") (pin "1") (pinfunction "1_1") (pintype "passive"))
      (node (ref "FB7") (pin "2") (pinfunction "2_2") (pintype "passive"))
      (node (ref "U4") (pin "16") (pinfunction "VDD_16") (pintype "power_in"))
      (node (ref "U4") (pin "20") (pinfunction "VCCO1V8_1_20") (pintype "power_in"))
      (node (ref "U4") (pin "29") (pinfunction "VCCO1V8_0_29") (pintype "power_in"))
    )
    (net (code "255") (name "VOUT_A") (class "Default")
      (node (ref "C56") (pin "1") (pinfunction "1_1") (pintype "passive"))
      (node (ref "FB10") (pin "1") (pinfunction "1_1") (pintype "passive"))
      (node (ref "R18") (pin "2") (pinfunction "2_2") (pintype "passive"))
      (node (ref "U6") (pin "8") (pinfunction "VOUT_8") (pintype "output"))
    )
    (net (code "256") (name "VOUT_B") (class "Default")
      (node (ref "C58") (pin "1") (pinfunction "1_1") (pintype "passive"))
      (node (ref "FB11") (pin "1") (pinfunction "1_1") (pintype "passive"))
      (node (ref "R16") (pin "2") (pinfunction "2_2") (pintype "passive"))
      (node (ref "U9") (pin "8") (pinfunction "VOUT_8") (pintype "output"))
    )
    (net (code "257") (name "VSUP") (class "Default")
      (node (ref "C57") (pin "1") (pinfunction "1_1") (pintype "passive"))
      (node (ref "C59") (pin "1") (pinfunction "1_1") (pintype "passive"))
      (node (ref "JP2") (pin "2") (pinfunction "2_2") (pintype "passive"))
      (node (ref "U6") (pin "3") (pinfunction "VIN_3") (pintype "power_in"))
      (node (ref "U6") (pin "4") (pinfunction "VIN_4") (pintype "power_in"))
      (node (ref "U9") (pin "3") (pinfunction "VIN_3") (pintype "power_in"))
      (node (ref "U9") (pin "4") (pinfunction "VIN_4") (pintype "power_in"))
    )
    (net (code "258") (name "VXX") (class "Default")
      (node (ref "C53") (pin "1") (pinfunction "1_1") (pintype "passive"))
      (node (ref "FB17") (pin "2") (pinfunction "2_2") (pintype "passive"))
      (node (ref "U5") (pin "6") (pinfunction "VCC_6") (pintype "power_in"))
    )
    (net (code "259") (name "unconnected-(JP1-Pad12)") (class "Default")
      (node (ref "JP1") (pin "12") (pinfunction "12_12") (pintype "passive"))
    )
    (net (code "260") (name "unconnected-(JP1-Pad14)") (class "Default")
      (node (ref "JP1") (pin "14") (pinfunction "14_14") (pintype "passive"))
    )
    (net (code "261") (name "unconnected-(PCIE-NORTH-PWRGD-PadA11)") (class "Default")
      (node (ref "PCIE-NORTH") (pin "A11") (pinfunction "PWRGD_A11") (pintype "passive"))
    )
    (net (code "262") (name "unconnected-(PCIE-SOUTH-PWRGD-PadA11)") (class "Default")
      (node (ref "PCIE-SOUTH") (pin "A11") (pinfunction "PWRGD_A11") (pintype "passive"))
    )
    (net (code "263") (name "unconnected-(PCIE-SOUTH-SCL-PadB2)") (class "Default")
      (node (ref "PCIE-SOUTH") (pin "B2") (pinfunction "SCL_B2") (pintype "passive"))
    )
    (net (code "264") (name "unconnected-(PCIE-SOUTH-SDA-PadB1)") (class "Default")
      (node (ref "PCIE-SOUTH") (pin "B1") (pinfunction "SDA_B1") (pintype "passive"))
    )
    (net (code "265") (name "unconnected-(PCIE-SOUTH-V_I2C-PadB3)") (class "Default")
      (node (ref "PCIE-SOUTH") (pin "B3") (pinfunction "V_I2C_B3") (pintype "passive"))
    )
  )
)
